# keyBoard_B_-.net
KiCad netlist of a schematic drawn in EAGLE
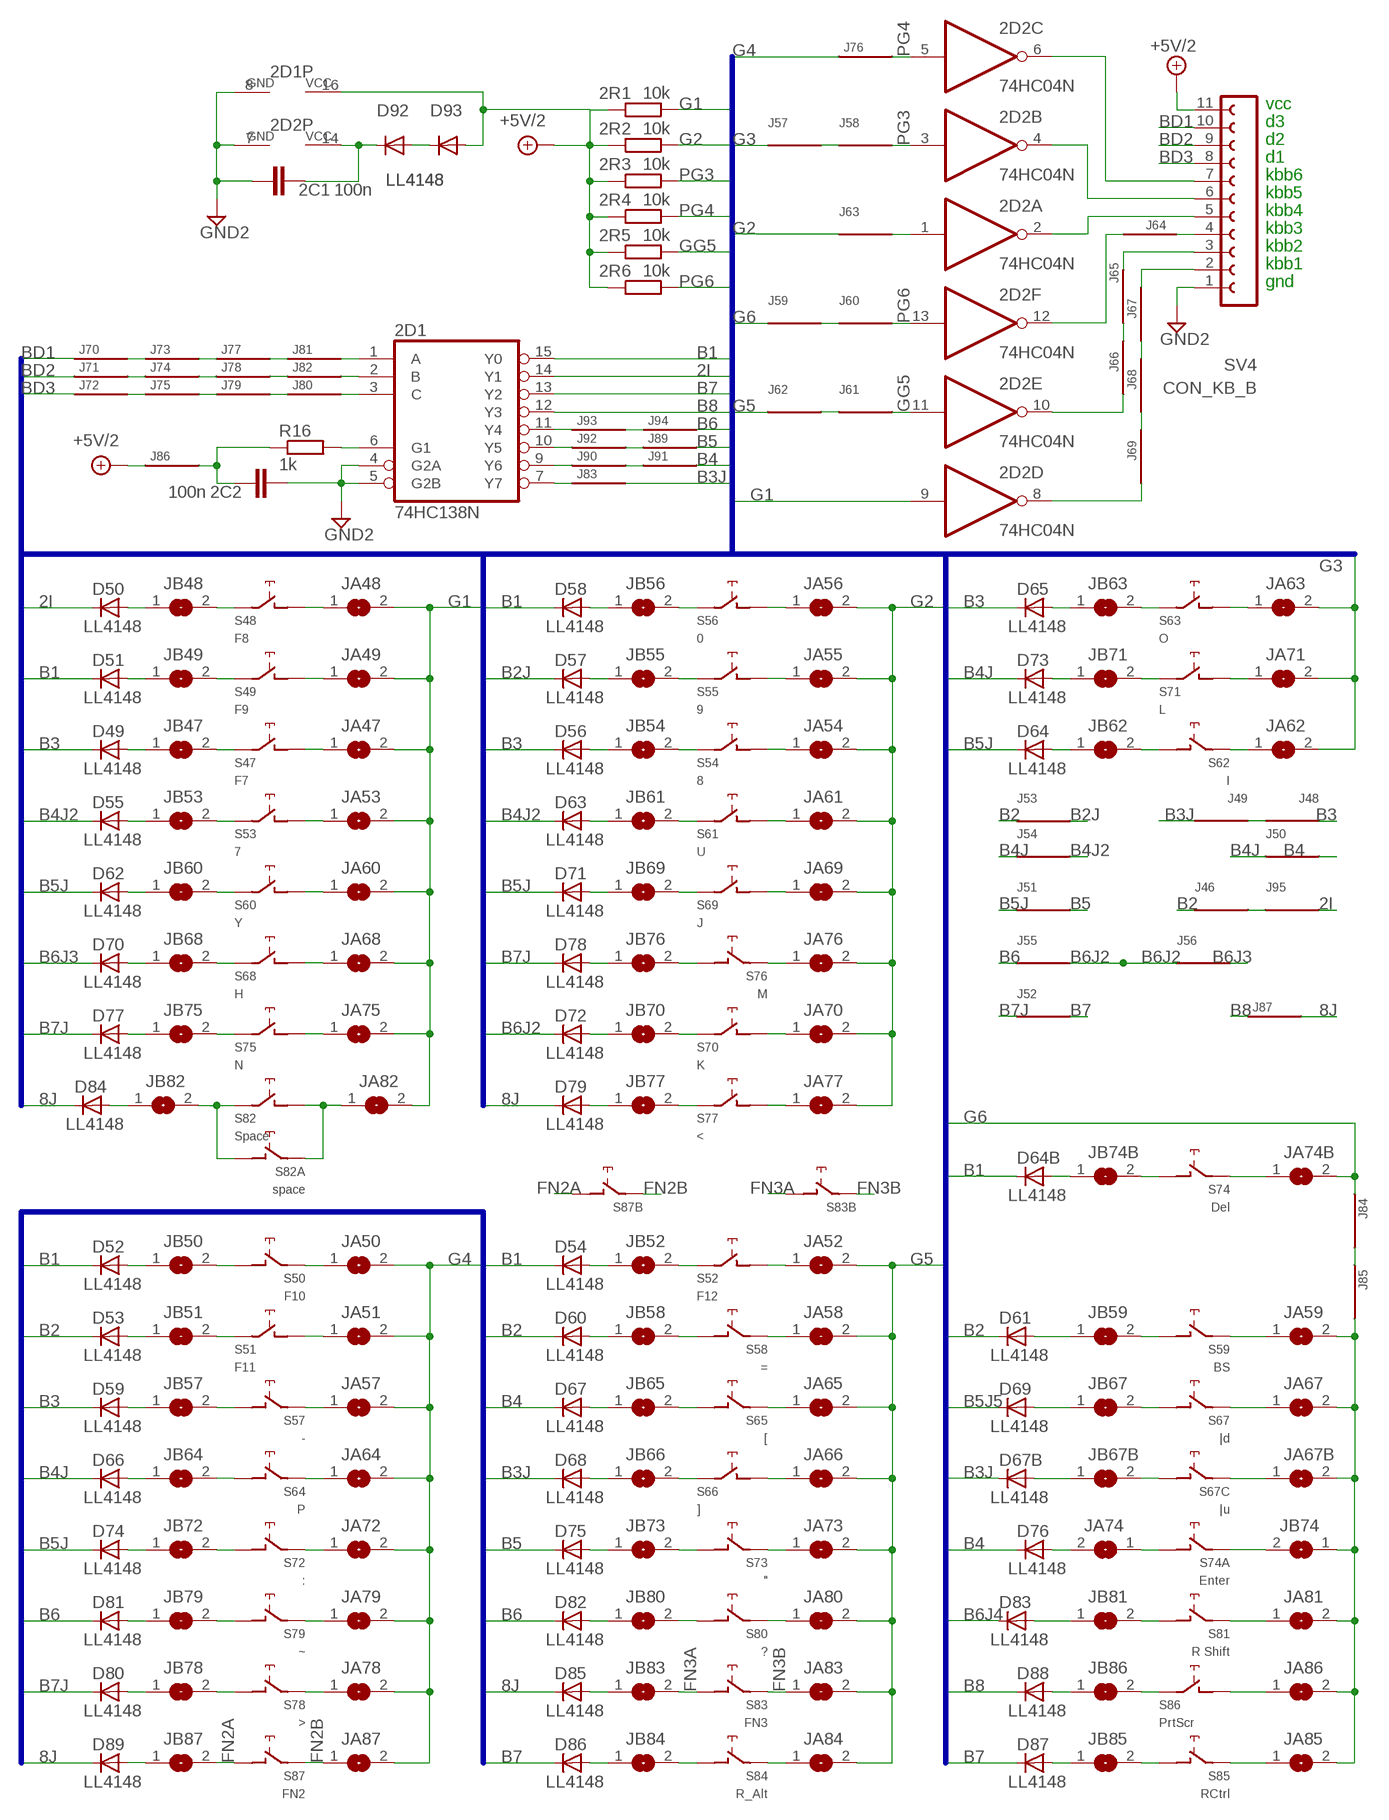
[diagram p0: schematic, sheet 1]

(export (version "E")
  (design (tool "Eeschema 10.0.6"))
  (components
    (comp (ref "2C1")
      (value "100n")
      (footprint "eagle-import:C1206")
      (libsource (lib "eagle-import") (part "C-EUC1206"))
    )
    (comp (ref "2C2")
      (value "100n")
      (footprint "eagle-import:C1206K")
      (libsource (lib "eagle-import") (part "C-EUC1206K"))
    )
    (comp (ref "2D1")
      (value "74HC138N")
      (footprint "eagle-import:DIL16")
      (libsource (lib "eagle-import") (part "74138NAC"))
    )
    (comp (ref "2D2")
      (value "74HC04N")
      (footprint "eagle-import:DIL14")
      (libsource (lib "eagle-import") (part "7404NALS"))
    )
    (comp (ref "2R1")
      (value "10k")
      (footprint "eagle-import:R0805")
      (libsource (lib "eagle-import") (part "R-EU_R0805"))
    )
    (comp (ref "2R2")
      (value "10k")
      (footprint "eagle-import:R0805")
      (libsource (lib "eagle-import") (part "R-EU_R0805"))
    )
    (comp (ref "2R3")
      (value "10k")
      (footprint "eagle-import:R0805")
      (libsource (lib "eagle-import") (part "R-EU_R0805"))
    )
    (comp (ref "2R4")
      (value "10k")
      (footprint "eagle-import:R1206W")
      (libsource (lib "eagle-import") (part "R-EU_R1206W"))
    )
    (comp (ref "2R5")
      (value "10k")
      (footprint "eagle-import:R0805")
      (libsource (lib "eagle-import") (part "R-EU_R0805"))
    )
    (comp (ref "2R6")
      (value "10k")
      (footprint "eagle-import:R0805")
      (libsource (lib "eagle-import") (part "R-EU_R0805"))
    )
    (comp (ref "D49")
      (value "LL4148")
      (footprint "eagle-import:SOD80C")
      (libsource (lib "eagle-import") (part "LL4148"))
    )
    (comp (ref "D50")
      (value "LL4148")
      (footprint "eagle-import:SOD80C")
      (libsource (lib "eagle-import") (part "LL4148"))
    )
    (comp (ref "D51")
      (value "LL4148")
      (footprint "eagle-import:SOD80C")
      (libsource (lib "eagle-import") (part "LL4148"))
    )
    (comp (ref "D52")
      (value "LL4148")
      (footprint "eagle-import:SOD80C")
      (libsource (lib "eagle-import") (part "LL4148"))
    )
    (comp (ref "D53")
      (value "LL4148")
      (footprint "eagle-import:SOD80C")
      (libsource (lib "eagle-import") (part "LL4148"))
    )
    (comp (ref "D54")
      (value "LL4148")
      (footprint "eagle-import:SOD80C")
      (libsource (lib "eagle-import") (part "LL4148"))
    )
    (comp (ref "D55")
      (value "LL4148")
      (footprint "eagle-import:SOD80C")
      (libsource (lib "eagle-import") (part "LL4148"))
    )
    (comp (ref "D56")
      (value "LL4148")
      (footprint "eagle-import:SOD80C")
      (libsource (lib "eagle-import") (part "LL4148"))
    )
    (comp (ref "D57")
      (value "LL4148")
      (footprint "eagle-import:SOD80C")
      (libsource (lib "eagle-import") (part "LL4148"))
    )
    (comp (ref "D58")
      (value "LL4148")
      (footprint "eagle-import:SOD80C")
      (libsource (lib "eagle-import") (part "LL4148"))
    )
    (comp (ref "D59")
      (value "LL4148")
      (footprint "eagle-import:SOD80C")
      (libsource (lib "eagle-import") (part "LL4148"))
    )
    (comp (ref "D60")
      (value "LL4148")
      (footprint "eagle-import:SOD80C")
      (libsource (lib "eagle-import") (part "LL4148"))
    )
    (comp (ref "D61")
      (value "LL4148")
      (footprint "eagle-import:SOD80C")
      (libsource (lib "eagle-import") (part "LL4148"))
    )
    (comp (ref "D62")
      (value "LL4148")
      (footprint "eagle-import:SOD80C")
      (libsource (lib "eagle-import") (part "LL4148"))
    )
    (comp (ref "D63")
      (value "LL4148")
      (footprint "eagle-import:SOD80C")
      (libsource (lib "eagle-import") (part "LL4148"))
    )
    (comp (ref "D64")
      (value "LL4148")
      (footprint "eagle-import:SOD80C")
      (libsource (lib "eagle-import") (part "LL4148"))
    )
    (comp (ref "D64B")
      (value "LL4148")
      (footprint "eagle-import:SOD80C")
      (libsource (lib "eagle-import") (part "LL4148"))
    )
    (comp (ref "D65")
      (value "LL4148")
      (footprint "eagle-import:SOD80C")
      (libsource (lib "eagle-import") (part "LL4148"))
    )
    (comp (ref "D66")
      (value "LL4148")
      (footprint "eagle-import:SOD80C")
      (libsource (lib "eagle-import") (part "LL4148"))
    )
    (comp (ref "D67")
      (value "LL4148")
      (footprint "eagle-import:SOD80C")
      (libsource (lib "eagle-import") (part "LL4148"))
    )
    (comp (ref "D67B")
      (value "LL4148")
      (footprint "eagle-import:SOD80C")
      (libsource (lib "eagle-import") (part "LL4148"))
    )
    (comp (ref "D68")
      (value "LL4148")
      (footprint "eagle-import:SOD80C")
      (libsource (lib "eagle-import") (part "LL4148"))
    )
    (comp (ref "D69")
      (value "LL4148")
      (footprint "eagle-import:SOD80C")
      (libsource (lib "eagle-import") (part "LL4148"))
    )
    (comp (ref "D70")
      (value "LL4148")
      (footprint "eagle-import:SOD80C")
      (libsource (lib "eagle-import") (part "LL4148"))
    )
    (comp (ref "D71")
      (value "LL4148")
      (footprint "eagle-import:SOD80C")
      (libsource (lib "eagle-import") (part "LL4148"))
    )
    (comp (ref "D72")
      (value "LL4148")
      (footprint "eagle-import:SOD80C")
      (libsource (lib "eagle-import") (part "LL4148"))
    )
    (comp (ref "D73")
      (value "LL4148")
      (footprint "eagle-import:SOD80C")
      (libsource (lib "eagle-import") (part "LL4148"))
    )
    (comp (ref "D74")
      (value "LL4148")
      (footprint "eagle-import:SOD80C")
      (libsource (lib "eagle-import") (part "LL4148"))
    )
    (comp (ref "D75")
      (value "LL4148")
      (footprint "eagle-import:SOD80C")
      (libsource (lib "eagle-import") (part "LL4148"))
    )
    (comp (ref "D76")
      (value "LL4148")
      (footprint "eagle-import:SOD80C")
      (libsource (lib "eagle-import") (part "LL4148"))
    )
    (comp (ref "D77")
      (value "LL4148")
      (footprint "eagle-import:SOD80C")
      (libsource (lib "eagle-import") (part "LL4148"))
    )
    (comp (ref "D78")
      (value "LL4148")
      (footprint "eagle-import:SOD80C")
      (libsource (lib "eagle-import") (part "LL4148"))
    )
    (comp (ref "D79")
      (value "LL4148")
      (footprint "eagle-import:SOD80C")
      (libsource (lib "eagle-import") (part "LL4148"))
    )
    (comp (ref "D80")
      (value "LL4148")
      (footprint "eagle-import:SOD80C")
      (libsource (lib "eagle-import") (part "LL4148"))
    )
    (comp (ref "D81")
      (value "LL4148")
      (footprint "eagle-import:SOD80C")
      (libsource (lib "eagle-import") (part "LL4148"))
    )
    (comp (ref "D82")
      (value "LL4148")
      (footprint "eagle-import:SOD80C")
      (libsource (lib "eagle-import") (part "LL4148"))
    )
    (comp (ref "D83")
      (value "LL4148")
      (footprint "eagle-import:SOD80C")
      (libsource (lib "eagle-import") (part "LL4148"))
    )
    (comp (ref "D84")
      (value "LL4148")
      (footprint "eagle-import:SOD80C")
      (libsource (lib "eagle-import") (part "LL4148"))
    )
    (comp (ref "D85")
      (value "LL4148")
      (footprint "eagle-import:SOD80C")
      (libsource (lib "eagle-import") (part "LL4148"))
    )
    (comp (ref "D86")
      (value "LL4148")
      (footprint "eagle-import:SOD80C")
      (libsource (lib "eagle-import") (part "LL4148"))
    )
    (comp (ref "D87")
      (value "LL4148")
      (footprint "eagle-import:SOD80C")
      (libsource (lib "eagle-import") (part "LL4148"))
    )
    (comp (ref "D88")
      (value "LL4148")
      (footprint "eagle-import:SOD80C")
      (libsource (lib "eagle-import") (part "LL4148"))
    )
    (comp (ref "D89")
      (value "LL4148")
      (footprint "eagle-import:SOD80C")
      (libsource (lib "eagle-import") (part "LL4148"))
    )
    (comp (ref "D92")
      (value "LL4148")
      (footprint "eagle-import:SOD80C")
      (libsource (lib "eagle-import") (part "LL4148"))
    )
    (comp (ref "D93")
      (value "LL4148")
      (footprint "eagle-import:SOD80C")
      (libsource (lib "eagle-import") (part "LL4148"))
    )
    (comp (ref "J46")
      (value "J")
      (footprint "eagle-import:R1206W")
      (libsource (lib "eagle-import") (part "J"))
    )
    (comp (ref "J48")
      (value "J")
      (footprint "eagle-import:R1206W")
      (libsource (lib "eagle-import") (part "J"))
    )
    (comp (ref "J49")
      (value "J")
      (footprint "eagle-import:R1206W")
      (libsource (lib "eagle-import") (part "J"))
    )
    (comp (ref "J50")
      (value "J")
      (footprint "eagle-import:R1206W")
      (libsource (lib "eagle-import") (part "J"))
    )
    (comp (ref "J51")
      (value "J")
      (footprint "eagle-import:R1206W")
      (libsource (lib "eagle-import") (part "J"))
    )
    (comp (ref "J52")
      (value "J")
      (footprint "eagle-import:R1206W")
      (libsource (lib "eagle-import") (part "J"))
    )
    (comp (ref "J53")
      (value "J")
      (footprint "eagle-import:R1206W")
      (libsource (lib "eagle-import") (part "J"))
    )
    (comp (ref "J54")
      (value "J")
      (footprint "eagle-import:R1206W")
      (libsource (lib "eagle-import") (part "J"))
    )
    (comp (ref "J55")
      (value "J")
      (footprint "eagle-import:R1206W")
      (libsource (lib "eagle-import") (part "J"))
    )
    (comp (ref "J56")
      (value "J")
      (footprint "eagle-import:R1206W")
      (libsource (lib "eagle-import") (part "J"))
    )
    (comp (ref "J57")
      (value "J")
      (footprint "eagle-import:R1206W")
      (libsource (lib "eagle-import") (part "J"))
    )
    (comp (ref "J58")
      (value "J")
      (footprint "eagle-import:R1206W")
      (libsource (lib "eagle-import") (part "J"))
    )
    (comp (ref "J59")
      (value "J")
      (footprint "eagle-import:R1206W")
      (libsource (lib "eagle-import") (part "J"))
    )
    (comp (ref "J60")
      (value "J")
      (footprint "eagle-import:R1206W")
      (libsource (lib "eagle-import") (part "J"))
    )
    (comp (ref "J61")
      (value "J")
      (footprint "eagle-import:R1206W")
      (libsource (lib "eagle-import") (part "J"))
    )
    (comp (ref "J62")
      (value "J")
      (footprint "eagle-import:R1206W")
      (libsource (lib "eagle-import") (part "J"))
    )
    (comp (ref "J63")
      (value "J")
      (footprint "eagle-import:R1206W")
      (libsource (lib "eagle-import") (part "J"))
    )
    (comp (ref "J64")
      (value "J")
      (footprint "eagle-import:R1206W")
      (libsource (lib "eagle-import") (part "J"))
    )
    (comp (ref "J65")
      (value "J")
      (footprint "eagle-import:R1206W")
      (libsource (lib "eagle-import") (part "J"))
    )
    (comp (ref "J66")
      (value "J")
      (footprint "eagle-import:R1206W")
      (libsource (lib "eagle-import") (part "J"))
    )
    (comp (ref "J67")
      (value "J")
      (footprint "eagle-import:R1206W")
      (libsource (lib "eagle-import") (part "J"))
    )
    (comp (ref "J68")
      (value "J")
      (footprint "eagle-import:R1206W")
      (libsource (lib "eagle-import") (part "J"))
    )
    (comp (ref "J69")
      (value "J")
      (footprint "eagle-import:R1206W")
      (libsource (lib "eagle-import") (part "J"))
    )
    (comp (ref "J70")
      (value "J")
      (footprint "eagle-import:R1206W")
      (libsource (lib "eagle-import") (part "J"))
    )
    (comp (ref "J71")
      (value "J")
      (footprint "eagle-import:R1206W")
      (libsource (lib "eagle-import") (part "J"))
    )
    (comp (ref "J72")
      (value "J")
      (footprint "eagle-import:R1206W")
      (libsource (lib "eagle-import") (part "J"))
    )
    (comp (ref "J73")
      (value "J")
      (footprint "eagle-import:R1206W")
      (libsource (lib "eagle-import") (part "J"))
    )
    (comp (ref "J74")
      (value "J")
      (footprint "eagle-import:R1206W")
      (libsource (lib "eagle-import") (part "J"))
    )
    (comp (ref "J75")
      (value "J")
      (footprint "eagle-import:R1206W")
      (libsource (lib "eagle-import") (part "J"))
    )
    (comp (ref "J76")
      (value "J")
      (footprint "eagle-import:R1206W")
      (libsource (lib "eagle-import") (part "J"))
    )
    (comp (ref "J77")
      (value "J")
      (footprint "eagle-import:R1206W")
      (libsource (lib "eagle-import") (part "J"))
    )
    (comp (ref "J78")
      (value "J")
      (footprint "eagle-import:R1206W")
      (libsource (lib "eagle-import") (part "J"))
    )
    (comp (ref "J79")
      (value "J")
      (footprint "eagle-import:R1206W")
      (libsource (lib "eagle-import") (part "J"))
    )
    (comp (ref "J80")
      (value "J")
      (footprint "eagle-import:R1206W")
      (libsource (lib "eagle-import") (part "J"))
    )
    (comp (ref "J81")
      (value "J")
      (footprint "eagle-import:R1206W")
      (libsource (lib "eagle-import") (part "J"))
    )
    (comp (ref "J82")
      (value "J")
      (footprint "eagle-import:R1206W")
      (libsource (lib "eagle-import") (part "J"))
    )
    (comp (ref "J83")
      (value "J")
      (footprint "eagle-import:R1206W")
      (libsource (lib "eagle-import") (part "J"))
    )
    (comp (ref "J84")
      (value "J")
      (footprint "eagle-import:R1206W")
      (libsource (lib "eagle-import") (part "J"))
    )
    (comp (ref "J85")
      (value "J")
      (footprint "eagle-import:R1206W")
      (libsource (lib "eagle-import") (part "J"))
    )
    (comp (ref "J86")
      (value "J")
      (footprint "eagle-import:R1206W")
      (libsource (lib "eagle-import") (part "J"))
    )
    (comp (ref "J87")
      (value "J")
      (footprint "eagle-import:R1206W")
      (libsource (lib "eagle-import") (part "J"))
    )
    (comp (ref "J89")
      (value "J")
      (footprint "eagle-import:R1206W")
      (libsource (lib "eagle-import") (part "J"))
    )
    (comp (ref "J90")
      (value "J")
      (footprint "eagle-import:R1206W")
      (libsource (lib "eagle-import") (part "J"))
    )
    (comp (ref "J91")
      (value "J")
      (footprint "eagle-import:R1206W")
      (libsource (lib "eagle-import") (part "J"))
    )
    (comp (ref "J92")
      (value "J")
      (footprint "eagle-import:R1206W")
      (libsource (lib "eagle-import") (part "J"))
    )
    (comp (ref "J93")
      (value "J")
      (footprint "eagle-import:R1206W")
      (libsource (lib "eagle-import") (part "J"))
    )
    (comp (ref "J94")
      (value "J")
      (footprint "eagle-import:R1206W")
      (libsource (lib "eagle-import") (part "J"))
    )
    (comp (ref "J95")
      (value "J")
      (footprint "eagle-import:R1206W")
      (libsource (lib "eagle-import") (part "J"))
    )
    (comp (ref "JA47")
      (value "SJ")
      (footprint "eagle-import:SJ")
      (libsource (lib "eagle-import") (part "SJ"))
    )
    (comp (ref "JA48")
      (value "SJ")
      (footprint "eagle-import:SJ")
      (libsource (lib "eagle-import") (part "SJ"))
    )
    (comp (ref "JA49")
      (value "SJ")
      (footprint "eagle-import:SJ")
      (libsource (lib "eagle-import") (part "SJ"))
    )
    (comp (ref "JA50")
      (value "SJ")
      (footprint "eagle-import:SJ")
      (libsource (lib "eagle-import") (part "SJ"))
    )
    (comp (ref "JA51")
      (value "SJ")
      (footprint "eagle-import:SJ")
      (libsource (lib "eagle-import") (part "SJ"))
    )
    (comp (ref "JA52")
      (value "SJ")
      (footprint "eagle-import:SJ")
      (libsource (lib "eagle-import") (part "SJ"))
    )
    (comp (ref "JA53")
      (value "SJ")
      (footprint "eagle-import:SJ")
      (libsource (lib "eagle-import") (part "SJ"))
    )
    (comp (ref "JA54")
      (value "SJ")
      (footprint "eagle-import:SJ")
      (libsource (lib "eagle-import") (part "SJ"))
    )
    (comp (ref "JA55")
      (value "SJ")
      (footprint "eagle-import:SJ")
      (libsource (lib "eagle-import") (part "SJ"))
    )
    (comp (ref "JA56")
      (value "SJ")
      (footprint "eagle-import:SJ")
      (libsource (lib "eagle-import") (part "SJ"))
    )
    (comp (ref "JA57")
      (value "SJ")
      (footprint "eagle-import:SJ")
      (libsource (lib "eagle-import") (part "SJ"))
    )
    (comp (ref "JA58")
      (value "SJ")
      (footprint "eagle-import:SJ")
      (libsource (lib "eagle-import") (part "SJ"))
    )
    (comp (ref "JA59")
      (value "SJ")
      (footprint "eagle-import:SJ")
      (libsource (lib "eagle-import") (part "SJ"))
    )
    (comp (ref "JA60")
      (value "SJ")
      (footprint "eagle-import:SJ")
      (libsource (lib "eagle-import") (part "SJ"))
    )
    (comp (ref "JA61")
      (value "SJ")
      (footprint "eagle-import:SJ")
      (libsource (lib "eagle-import") (part "SJ"))
    )
    (comp (ref "JA62")
      (value "SJ")
      (footprint "eagle-import:SJ")
      (libsource (lib "eagle-import") (part "SJ"))
    )
    (comp (ref "JA63")
      (value "SJ")
      (footprint "eagle-import:SJ")
      (libsource (lib "eagle-import") (part "SJ"))
    )
    (comp (ref "JA64")
      (value "SJ")
      (footprint "eagle-import:SJ")
      (libsource (lib "eagle-import") (part "SJ"))
    )
    (comp (ref "JA65")
      (value "SJ")
      (footprint "eagle-import:SJ")
      (libsource (lib "eagle-import") (part "SJ"))
    )
    (comp (ref "JA66")
      (value "SJ")
      (footprint "eagle-import:SJ")
      (libsource (lib "eagle-import") (part "SJ"))
    )
    (comp (ref "JA67")
      (value "SJ")
      (footprint "eagle-import:SJ")
      (libsource (lib "eagle-import") (part "SJ"))
    )
    (comp (ref "JA67B")
      (value "SJ")
      (footprint "eagle-import:SJ")
      (libsource (lib "eagle-import") (part "SJ"))
    )
    (comp (ref "JA68")
      (value "SJ")
      (footprint "eagle-import:SJ")
      (libsource (lib "eagle-import") (part "SJ"))
    )
    (comp (ref "JA69")
      (value "SJ")
      (footprint "eagle-import:SJ")
      (libsource (lib "eagle-import") (part "SJ"))
    )
    (comp (ref "JA70")
      (value "SJ")
      (footprint "eagle-import:SJ")
      (libsource (lib "eagle-import") (part "SJ"))
    )
    (comp (ref "JA71")
      (value "SJ")
      (footprint "eagle-import:SJ")
      (libsource (lib "eagle-import") (part "SJ"))
    )
    (comp (ref "JA72")
      (value "SJ")
      (footprint "eagle-import:SJ")
      (libsource (lib "eagle-import") (part "SJ"))
    )
    (comp (ref "JA73")
      (value "SJ")
      (footprint "eagle-import:SJ")
      (libsource (lib "eagle-import") (part "SJ"))
    )
    (comp (ref "JA74")
      (value "SJ")
      (footprint "eagle-import:SJ")
      (libsource (lib "eagle-import") (part "SJ"))
    )
    (comp (ref "JA74B")
      (value "SJ")
      (footprint "eagle-import:SJ")
      (libsource (lib "eagle-import") (part "SJ"))
    )
    (comp (ref "JA75")
      (value "SJ")
      (footprint "eagle-import:SJ")
      (libsource (lib "eagle-import") (part "SJ"))
    )
    (comp (ref "JA76")
      (value "SJ")
      (footprint "eagle-import:SJ")
      (libsource (lib "eagle-import") (part "SJ"))
    )
    (comp (ref "JA77")
      (value "SJ")
      (footprint "eagle-import:SJ")
      (libsource (lib "eagle-import") (part "SJ"))
    )
    (comp (ref "JA78")
      (value "SJ")
      (footprint "eagle-import:SJ")
      (libsource (lib "eagle-import") (part "SJ"))
    )
    (comp (ref "JA79")
      (value "SJ")
      (footprint "eagle-import:SJ")
      (libsource (lib "eagle-import") (part "SJ"))
    )
    (comp (ref "JA80")
      (value "SJ")
      (footprint "eagle-import:SJ")
      (libsource (lib "eagle-import") (part "SJ"))
    )
    (comp (ref "JA81")
      (value "SJ")
      (footprint "eagle-import:SJ")
      (libsource (lib "eagle-import") (part "SJ"))
    )
    (comp (ref "JA82")
      (value "SJ")
      (footprint "eagle-import:SJ")
      (libsource (lib "eagle-import") (part "SJ"))
    )
    (comp (ref "JA83")
      (value "SJ")
      (footprint "eagle-import:SJ")
      (libsource (lib "eagle-import") (part "SJ"))
    )
    (comp (ref "JA84")
      (value "SJ")
      (footprint "eagle-import:SJ")
      (libsource (lib "eagle-import") (part "SJ"))
    )
    (comp (ref "JA85")
      (value "SJ")
      (footprint "eagle-import:SJ")
      (libsource (lib "eagle-import") (part "SJ"))
    )
    (comp (ref "JA86")
      (value "SJ")
      (footprint "eagle-import:SJ")
      (libsource (lib "eagle-import") (part "SJ"))
    )
    (comp (ref "JA87")
      (value "SJ")
      (footprint "eagle-import:SJ")
      (libsource (lib "eagle-import") (part "SJ"))
    )
    (comp (ref "JB47")
      (value "SJ")
      (footprint "eagle-import:SJ")
      (libsource (lib "eagle-import") (part "SJ"))
    )
    (comp (ref "JB48")
      (value "SJ")
      (footprint "eagle-import:SJ")
      (libsource (lib "eagle-import") (part "SJ"))
    )
    (comp (ref "JB49")
      (value "SJ")
      (footprint "eagle-import:SJ")
      (libsource (lib "eagle-import") (part "SJ"))
    )
    (comp (ref "JB50")
      (value "SJ")
      (footprint "eagle-import:SJ")
      (libsource (lib "eagle-import") (part "SJ"))
    )
    (comp (ref "JB51")
      (value "SJ")
      (footprint "eagle-import:SJ")
      (libsource (lib "eagle-import") (part "SJ"))
    )
    (comp (ref "JB52")
      (value "SJ")
      (footprint "eagle-import:SJ")
      (libsource (lib "eagle-import") (part "SJ"))
    )
    (comp (ref "JB53")
      (value "SJ")
      (footprint "eagle-import:SJ")
      (libsource (lib "eagle-import") (part "SJ"))
    )
    (comp (ref "JB54")
      (value "SJ")
      (footprint "eagle-import:SJ")
      (libsource (lib "eagle-import") (part "SJ"))
    )
    (comp (ref "JB55")
      (value "SJ")
      (footprint "eagle-import:SJ")
      (libsource (lib "eagle-import") (part "SJ"))
    )
    (comp (ref "JB56")
      (value "SJ")
      (footprint "eagle-import:SJ")
      (libsource (lib "eagle-import") (part "SJ"))
    )
    (comp (ref "JB57")
      (value "SJ")
      (footprint "eagle-import:SJ")
      (libsource (lib "eagle-import") (part "SJ"))
    )
    (comp (ref "JB58")
      (value "SJ")
      (footprint "eagle-import:SJ")
      (libsource (lib "eagle-import") (part "SJ"))
    )
    (comp (ref "JB59")
      (value "SJ")
      (footprint "eagle-import:SJ")
      (libsource (lib "eagle-import") (part "SJ"))
    )
    (comp (ref "JB60")
      (value "SJ")
      (footprint "eagle-import:SJ")
      (libsource (lib "eagle-import") (part "SJ"))
    )
    (comp (ref "JB61")
      (value "SJ")
      (footprint "eagle-import:SJ")
      (libsource (lib "eagle-import") (part "SJ"))
    )
    (comp (ref "JB62")
      (value "SJ")
      (footprint "eagle-import:SJ")
      (libsource (lib "eagle-import") (part "SJ"))
    )
    (comp (ref "JB63")
      (value "SJ")
      (footprint "eagle-import:SJ")
      (libsource (lib "eagle-import") (part "SJ"))
    )
    (comp (ref "JB64")
      (value "SJ")
      (footprint "eagle-import:SJ")
      (libsource (lib "eagle-import") (part "SJ"))
    )
    (comp (ref "JB65")
      (value "SJ")
      (footprint "eagle-import:SJ")
      (libsource (lib "eagle-import") (part "SJ"))
    )
    (comp (ref "JB66")
      (value "SJ")
      (footprint "eagle-import:SJ")
      (libsource (lib "eagle-import") (part "SJ"))
    )
    (comp (ref "JB67")
      (value "SJ")
      (footprint "eagle-import:SJ")
      (libsource (lib "eagle-import") (part "SJ"))
    )
    (comp (ref "JB67B")
      (value "SJ")
      (footprint "eagle-import:SJ")
      (libsource (lib "eagle-import") (part "SJ"))
    )
    (comp (ref "JB68")
      (value "SJ")
      (footprint "eagle-import:SJ")
      (libsource (lib "eagle-import") (part "SJ"))
    )
    (comp (ref "JB69")
      (value "SJ")
      (footprint "eagle-import:SJ")
      (libsource (lib "eagle-import") (part "SJ"))
    )
    (comp (ref "JB70")
      (value "SJ")
      (footprint "eagle-import:SJ")
      (libsource (lib "eagle-import") (part "SJ"))
    )
    (comp (ref "JB71")
      (value "SJ")
      (footprint "eagle-import:SJ")
      (libsource (lib "eagle-import") (part "SJ"))
    )
    (comp (ref "JB72")
      (value "SJ")
      (footprint "eagle-import:SJ")
      (libsource (lib "eagle-import") (part "SJ"))
    )
    (comp (ref "JB73")
      (value "SJ")
      (footprint "eagle-import:SJ")
      (libsource (lib "eagle-import") (part "SJ"))
    )
    (comp (ref "JB74")
      (value "SJ")
      (footprint "eagle-import:SJ")
      (libsource (lib "eagle-import") (part "SJ"))
    )
    (comp (ref "JB74B")
      (value "SJ")
      (footprint "eagle-import:SJ")
      (libsource (lib "eagle-import") (part "SJ"))
    )
    (comp (ref "JB75")
      (value "SJ")
      (footprint "eagle-import:SJ")
      (libsource (lib "eagle-import") (part "SJ"))
    )
    (comp (ref "JB76")
      (value "SJ")
      (footprint "eagle-import:SJ")
      (libsource (lib "eagle-import") (part "SJ"))
    )
    (comp (ref "JB77")
      (value "SJ")
      (footprint "eagle-import:SJ")
      (libsource (lib "eagle-import") (part "SJ"))
    )
    (comp (ref "JB78")
      (value "SJ")
      (footprint "eagle-import:SJ")
      (libsource (lib "eagle-import") (part "SJ"))
    )
    (comp (ref "JB79")
      (value "SJ")
      (footprint "eagle-import:SJ")
      (libsource (lib "eagle-import") (part "SJ"))
    )
    (comp (ref "JB80")
      (value "SJ")
      (footprint "eagle-import:SJ")
      (libsource (lib "eagle-import") (part "SJ"))
    )
    (comp (ref "JB81")
      (value "SJ")
      (footprint "eagle-import:SJ")
      (libsource (lib "eagle-import") (part "SJ"))
    )
    (comp (ref "JB82")
      (value "SJ")
      (footprint "eagle-import:SJ")
      (libsource (lib "eagle-import") (part "SJ"))
    )
    (comp (ref "JB83")
      (value "SJ")
      (footprint "eagle-import:SJ")
      (libsource (lib "eagle-import") (part "SJ"))
    )
    (comp (ref "JB84")
      (value "SJ")
      (footprint "eagle-import:SJ")
      (libsource (lib "eagle-import") (part "SJ"))
    )
    (comp (ref "JB85")
      (value "SJ")
      (footprint "eagle-import:SJ")
      (libsource (lib "eagle-import") (part "SJ"))
    )
    (comp (ref "JB86")
      (value "SJ")
      (footprint "eagle-import:SJ")
      (libsource (lib "eagle-import") (part "SJ"))
    )
    (comp (ref "JB87")
      (value "SJ")
      (footprint "eagle-import:SJ")
      (libsource (lib "eagle-import") (part "SJ"))
    )
    (comp (ref "R16")
      (value "1k")
      (footprint "eagle-import:R1206W")
      (libsource (lib "eagle-import") (part "R-EU_R1206W"))
    )
    (comp (ref "S47")
      (value "F7")
      (footprint "eagle-import:CHERRY-MX-4P")
      (libsource (lib "eagle-import") (part "CHERRY-MX-4P"))
    )
    (comp (ref "S48")
      (value "F8")
      (footprint "eagle-import:CHERRY-MX-4P")
      (libsource (lib "eagle-import") (part "CHERRY-MX-4P"))
    )
    (comp (ref "S49")
      (value "F9")
      (footprint "eagle-import:CHERRY-MX-4P")
      (libsource (lib "eagle-import") (part "CHERRY-MX-4P"))
    )
    (comp (ref "S50")
      (value "F10")
      (footprint "eagle-import:CHERRY-MX-4P")
      (libsource (lib "eagle-import") (part "CHERRY-MX-4P"))
    )
    (comp (ref "S51")
      (value "F11")
      (footprint "eagle-import:CHERRY-MX-4P")
      (libsource (lib "eagle-import") (part "CHERRY-MX-4P"))
    )
    (comp (ref "S52")
      (value "F12")
      (footprint "eagle-import:CHERRY-MX-4P")
      (libsource (lib "eagle-import") (part "CHERRY-MX-4P"))
    )
    (comp (ref "S53")
      (value "7")
      (footprint "eagle-import:CHERRY-MX-4P")
      (libsource (lib "eagle-import") (part "CHERRY-MX-4P"))
    )
    (comp (ref "S54")
      (value "8")
      (footprint "eagle-import:CHERRY-MX-4P")
      (libsource (lib "eagle-import") (part "CHERRY-MX-4P"))
    )
    (comp (ref "S55")
      (value "9")
      (footprint "eagle-import:CHERRY-MX-4P")
      (libsource (lib "eagle-import") (part "CHERRY-MX-4P"))
    )
    (comp (ref "S56")
      (value "0")
      (footprint "eagle-import:CHERRY-MX-4P")
      (libsource (lib "eagle-import") (part "CHERRY-MX-4P"))
    )
    (comp (ref "S57")
      (value "-")
      (footprint "eagle-import:CHERRY-MX-4P")
      (libsource (lib "eagle-import") (part "CHERRY-MX-4P"))
    )
    (comp (ref "S58")
      (value "=")
      (footprint "eagle-import:CHERRY-MX-4P")
      (libsource (lib "eagle-import") (part "CHERRY-MX-4P"))
    )
    (comp (ref "S59")
      (value "BS")
      (footprint "eagle-import:CHERRY-MX-4P")
      (libsource (lib "eagle-import") (part "CHERRY-MX-4P"))
    )
    (comp (ref "S60")
      (value "Y")
      (footprint "eagle-import:CHERRY-MX-4P")
      (libsource (lib "eagle-import") (part "CHERRY-MX-4P"))
    )
    (comp (ref "S61")
      (value "U")
      (footprint "eagle-import:CHERRY-MX-4P")
      (libsource (lib "eagle-import") (part "CHERRY-MX-4P"))
    )
    (comp (ref "S62")
      (value "I")
      (footprint "eagle-import:CHERRY-MX-4P")
      (libsource (lib "eagle-import") (part "CHERRY-MX-4P"))
    )
    (comp (ref "S63")
      (value "O")
      (footprint "eagle-import:CHERRY-MX-4P")
      (libsource (lib "eagle-import") (part "CHERRY-MX-4P"))
    )
    (comp (ref "S64")
      (value "P")
      (footprint "eagle-import:CHERRY-MX-4P")
      (libsource (lib "eagle-import") (part "CHERRY-MX-4P"))
    )
    (comp (ref "S65")
      (value "[")
      (footprint "eagle-import:CHERRY-MX-4P")
      (libsource (lib "eagle-import") (part "CHERRY-MX-4P"))
    )
    (comp (ref "S66")
      (value "]")
      (footprint "eagle-import:CHERRY-MX-4P")
      (libsource (lib "eagle-import") (part "CHERRY-MX-4P"))
    )
    (comp (ref "S67")
      (value "|d")
      (footprint "eagle-import:CHERRY-MX-4P")
      (libsource (lib "eagle-import") (part "CHERRY-MX-4P"))
    )
    (comp (ref "S67C")
      (value "|u")
      (footprint "eagle-import:CHERRY-MX-4P")
      (libsource (lib "eagle-import") (part "CHERRY-MX-4P"))
    )
    (comp (ref "S68")
      (value "H")
      (footprint "eagle-import:CHERRY-MX-4P")
      (libsource (lib "eagle-import") (part "CHERRY-MX-4P"))
    )
    (comp (ref "S69")
      (value "J")
      (footprint "eagle-import:CHERRY-MX-4P")
      (libsource (lib "eagle-import") (part "CHERRY-MX-4P"))
    )
    (comp (ref "S70")
      (value "K")
      (footprint "eagle-import:CHERRY-MX-4P")
      (libsource (lib "eagle-import") (part "CHERRY-MX-4P"))
    )
    (comp (ref "S71")
      (value "L")
      (footprint "eagle-import:CHERRY-MX-4P")
      (libsource (lib "eagle-import") (part "CHERRY-MX-4P"))
    )
    (comp (ref "S72")
      (value ":")
      (footprint "eagle-import:CHERRY-MX-4P")
      (libsource (lib "eagle-import") (part "CHERRY-MX-4P"))
    )
    (comp (ref "S73")
      (value "\"")
      (footprint "eagle-import:CHERRY-MX-4P")
      (libsource (lib "eagle-import") (part "CHERRY-MX-4P"))
    )
    (comp (ref "S74")
      (value "Del")
      (footprint "eagle-import:CHERRY-MX-4P")
      (libsource (lib "eagle-import") (part "CHERRY-MX-4P"))
    )
    (comp (ref "S74A")
      (value "Enter")
      (footprint "eagle-import:CHERRY-MX-4P")
      (libsource (lib "eagle-import") (part "CHERRY-MX-4P"))
    )
    (comp (ref "S75")
      (value "N")
      (footprint "eagle-import:CHERRY-MX-4P")
      (libsource (lib "eagle-import") (part "CHERRY-MX-4P"))
    )
    (comp (ref "S76")
      (value "M")
      (footprint "eagle-import:CHERRY-MX-4P")
      (libsource (lib "eagle-import") (part "CHERRY-MX-4P"))
    )
    (comp (ref "S77")
      (value "<")
      (footprint "eagle-import:CHERRY-MX-4P")
      (libsource (lib "eagle-import") (part "CHERRY-MX-4P"))
    )
    (comp (ref "S78")
      (value ">")
      (footprint "eagle-import:CHERRY-MX-4P")
      (libsource (lib "eagle-import") (part "CHERRY-MX-4P"))
    )
    (comp (ref "S79")
      (value "~")
      (footprint "eagle-import:CHERRY-MX-4P")
      (libsource (lib "eagle-import") (part "CHERRY-MX-4P"))
    )
    (comp (ref "S80")
      (value "?")
      (footprint "eagle-import:CHERRY-MX-4P")
      (libsource (lib "eagle-import") (part "CHERRY-MX-4P"))
    )
    (comp (ref "S81")
      (value "R Shift")
      (footprint "eagle-import:CHERRY-MX-4P")
      (libsource (lib "eagle-import") (part "CHERRY-MX-4P"))
    )
    (comp (ref "S82")
      (value "Space")
      (footprint "eagle-import:CHERRY-MX-4P")
      (libsource (lib "eagle-import") (part "CHERRY-MX-4P"))
    )
    (comp (ref "S82A")
      (value "space")
      (footprint "eagle-import:CHERRY-MX")
      (libsource (lib "eagle-import") (part "CHERRY-MX"))
    )
    (comp (ref "S83")
      (value "FN3")
      (footprint "eagle-import:CHERRY-MX-4P")
      (libsource (lib "eagle-import") (part "CHERRY-MX-4P"))
    )
    (comp (ref "S83B")
      (value "CHERRY-MX")
      (footprint "eagle-import:CHERRY-MX")
      (libsource (lib "eagle-import") (part "CHERRY-MX"))
    )
    (comp (ref "S84")
      (value "R_Alt")
      (footprint "eagle-import:CHERRY-MX-4P")
      (libsource (lib "eagle-import") (part "CHERRY-MX-4P"))
    )
    (comp (ref "S85")
      (value "RCtrl")
      (footprint "eagle-import:CHERRY-MX-4P")
      (libsource (lib "eagle-import") (part "CHERRY-MX-4P"))
    )
    (comp (ref "S86")
      (value "PrtScr")
      (footprint "eagle-import:CHERRY-MX-4P")
      (libsource (lib "eagle-import") (part "CHERRY-MX-4P"))
    )
    (comp (ref "S87")
      (value "FN2")
      (footprint "eagle-import:CHERRY-MX-4P")
      (libsource (lib "eagle-import") (part "CHERRY-MX-4P"))
    )
    (comp (ref "S87B")
      (value "CHERRY-MX")
      (footprint "eagle-import:CHERRY-MX")
      (libsource (lib "eagle-import") (part "CHERRY-MX"))
    )
    (comp (ref "SV4")
      (value "CON_KB_B")
      (footprint "eagle-import:FE12")
      (libsource (lib "eagle-import") (part "FE12-1"))
    )
  )
  (nets
    (net (code "4") (name "+5V{slash}2") (class "Default")
      (node (ref "2D1") (pin "16") (pinfunction "VCC_16") (pintype "power_in"))
      (node (ref "2R1") (pin "1") (pinfunction "1_1") (pintype "passive"))
      (node (ref "2R2") (pin "1") (pinfunction "1_1") (pintype "passive"))
      (node (ref "2R3") (pin "1") (pinfunction "1_1") (pintype "passive"))
      (node (ref "2R4") (pin "1") (pinfunction "1_1") (pintype "passive"))
      (node (ref "2R5") (pin "1") (pinfunction "1_1") (pintype "passive"))
      (node (ref "2R6") (pin "1") (pinfunction "1_1") (pintype "passive"))
      (node (ref "D93") (pin "A") (pinfunction "A_A") (pintype "passive"))
      (node (ref "J86") (pin "2") (pinfunction "P$2_2") (pintype "bidirectional"))
      (node (ref "SV4") (pin "11") (pinfunction "11_11") (pintype "passive"))
    )
    (net (code "5") (name "/2I") (class "Default")
      (node (ref "2D1") (pin "14") (pinfunction "Y1_14") (pintype "output"))
      (node (ref "D50") (pin "C") (pinfunction "C_C") (pintype "passive"))
      (node (ref "J95") (pin "1") (pinfunction "P$1_1") (pintype "bidirectional"))
    )
    (net (code "6") (name "/8J") (class "Default")
      (node (ref "D79") (pin "C") (pinfunction "C_C") (pintype "passive"))
      (node (ref "D84") (pin "C") (pinfunction "C_C") (pintype "passive"))
      (node (ref "D85") (pin "C") (pinfunction "C_C") (pintype "passive"))
      (node (ref "D89") (pin "C") (pinfunction "C_C") (pintype "passive"))
      (node (ref "J87") (pin "1") (pinfunction "P$1_1") (pintype "bidirectional"))
    )
    (net (code "7") (name "/B1") (class "Default")
      (node (ref "2D1") (pin "15") (pinfunction "Y0_15") (pintype "output"))
      (node (ref "D51") (pin "C") (pinfunction "C_C") (pintype "passive"))
      (node (ref "D52") (pin "C") (pinfunction "C_C") (pintype "passive"))
      (node (ref "D54") (pin "C") (pinfunction "C_C") (pintype "passive"))
      (node (ref "D58") (pin "C") (pinfunction "C_C") (pintype "passive"))
      (node (ref "D64B") (pin "C") (pinfunction "C_C") (pintype "passive"))
    )
    (net (code "8") (name "/B2") (class "Default")
      (node (ref "D53") (pin "C") (pinfunction "C_C") (pintype "passive"))
      (node (ref "D60") (pin "C") (pinfunction "C_C") (pintype "passive"))
      (node (ref "D61") (pin "C") (pinfunction "C_C") (pintype "passive"))
      (node (ref "J46") (pin "2") (pinfunction "P$2_2") (pintype "bidirectional"))
      (node (ref "J53") (pin "2") (pinfunction "P$2_2") (pintype "bidirectional"))
    )
    (net (code "9") (name "/B2J") (class "Default")
      (node (ref "D57") (pin "C") (pinfunction "C_C") (pintype "passive"))
      (node (ref "J53") (pin "1") (pinfunction "P$1_1") (pintype "bidirectional"))
    )
    (net (code "10") (name "/B3") (class "Default")
      (node (ref "D49") (pin "C") (pinfunction "C_C") (pintype "passive"))
      (node (ref "D56") (pin "C") (pinfunction "C_C") (pintype "passive"))
      (node (ref "D59") (pin "C") (pinfunction "C_C") (pintype "passive"))
      (node (ref "D65") (pin "C") (pinfunction "C_C") (pintype "passive"))
      (node (ref "J48") (pin "2") (pinfunction "P$2_2") (pintype "bidirectional"))
    )
    (net (code "11") (name "/B3J") (class "Default")
      (node (ref "D67B") (pin "C") (pinfunction "C_C") (pintype "passive"))
      (node (ref "D68") (pin "C") (pinfunction "C_C") (pintype "passive"))
      (node (ref "J49") (pin "1") (pinfunction "P$1_1") (pintype "bidirectional"))
      (node (ref "J83") (pin "1") (pinfunction "P$1_1") (pintype "bidirectional"))
    )
    (net (code "12") (name "/B4") (class "Default")
      (node (ref "D67") (pin "C") (pinfunction "C_C") (pintype "passive"))
      (node (ref "D76") (pin "C") (pinfunction "C_C") (pintype "passive"))
      (node (ref "J50") (pin "1") (pinfunction "P$1_1") (pintype "bidirectional"))
      (node (ref "J91") (pin "1") (pinfunction "P$1_1") (pintype "bidirectional"))
    )
    (net (code "13") (name "/B4J") (class "Default")
      (node (ref "D66") (pin "C") (pinfunction "C_C") (pintype "passive"))
      (node (ref "D73") (pin "C") (pinfunction "C_C") (pintype "passive"))
      (node (ref "J50") (pin "2") (pinfunction "P$2_2") (pintype "bidirectional"))
      (node (ref "J54") (pin "2") (pinfunction "P$2_2") (pintype "bidirectional"))
    )
    (net (code "14") (name "/B4J2") (class "Default")
      (node (ref "D55") (pin "C") (pinfunction "C_C") (pintype "passive"))
      (node (ref "D63") (pin "C") (pinfunction "C_C") (pintype "passive"))
      (node (ref "J54") (pin "1") (pinfunction "P$1_1") (pintype "bidirectional"))
    )
    (net (code "15") (name "/B5") (class "Default")
      (node (ref "D75") (pin "C") (pinfunction "C_C") (pintype "passive"))
      (node (ref "J51") (pin "1") (pinfunction "P$1_1") (pintype "bidirectional"))
      (node (ref "J89") (pin "1") (pinfunction "P$1_1") (pintype "bidirectional"))
    )
    (net (code "16") (name "/B5J") (class "Default")
      (node (ref "D62") (pin "C") (pinfunction "C_C") (pintype "passive"))
      (node (ref "D64") (pin "C") (pinfunction "C_C") (pintype "passive"))
      (node (ref "D71") (pin "C") (pinfunction "C_C") (pintype "passive"))
      (node (ref "D74") (pin "C") (pinfunction "C_C") (pintype "passive"))
      (node (ref "J51") (pin "2") (pinfunction "P$2_2") (pintype "bidirectional"))
    )
    (net (code "17") (name "/B5J5") (class "Default")
      (node (ref "2D1") (pin "10") (pinfunction "Y5_10") (pintype "output"))
      (node (ref "D69") (pin "C") (pinfunction "C_C") (pintype "passive"))
      (node (ref "J92") (pin "2") (pinfunction "P$2_2") (pintype "bidirectional"))
    )
    (net (code "18") (name "/B6") (class "Default")
      (node (ref "D81") (pin "C") (pinfunction "C_C") (pintype "passive"))
      (node (ref "D82") (pin "C") (pinfunction "C_C") (pintype "passive"))
      (node (ref "J55") (pin "2") (pinfunction "P$2_2") (pintype "bidirectional"))
      (node (ref "J94") (pin "1") (pinfunction "P$1_1") (pintype "bidirectional"))
    )
    (net (code "19") (name "/B6J2") (class "Default")
      (node (ref "D72") (pin "C") (pinfunction "C_C") (pintype "passive"))
      (node (ref "J55") (pin "1") (pinfunction "P$1_1") (pintype "bidirectional"))
      (node (ref "J56") (pin "2") (pinfunction "P$2_2") (pintype "bidirectional"))
    )
    (net (code "20") (name "/B6J3") (class "Default")
      (node (ref "D70") (pin "C") (pinfunction "C_C") (pintype "passive"))
      (node (ref "J56") (pin "1") (pinfunction "P$1_1") (pintype "bidirectional"))
    )
    (net (code "21") (name "/B6J4") (class "Default")
      (node (ref "D83") (pin "C") (pinfunction "C_C") (pintype "passive"))
      (node (ref "J93") (pin "1") (pinfunction "P$1_1") (pintype "bidirectional"))
      (node (ref "J94") (pin "2") (pinfunction "P$2_2") (pintype "bidirectional"))
    )
    (net (code "22") (name "/B7") (class "Default")
      (node (ref "2D1") (pin "13") (pinfunction "Y2_13") (pintype "output"))
      (node (ref "D86") (pin "C") (pinfunction "C_C") (pintype "passive"))
      (node (ref "D87") (pin "C") (pinfunction "C_C") (pintype "passive"))
      (node (ref "J52") (pin "1") (pinfunction "P$1_1") (pintype "bidirectional"))
    )
    (net (code "23") (name "/B7J") (class "Default")
      (node (ref "D77") (pin "C") (pinfunction "C_C") (pintype "passive"))
      (node (ref "D78") (pin "C") (pinfunction "C_C") (pintype "passive"))
      (node (ref "D80") (pin "C") (pinfunction "C_C") (pintype "passive"))
      (node (ref "J52") (pin "2") (pinfunction "P$2_2") (pintype "bidirectional"))
    )
    (net (code "24") (name "/B8") (class "Default")
      (node (ref "2D1") (pin "12") (pinfunction "Y3_12") (pintype "output"))
      (node (ref "D88") (pin "C") (pinfunction "C_C") (pintype "passive"))
      (node (ref "J87") (pin "2") (pinfunction "P$2_2") (pintype "bidirectional"))
    )
    (net (code "25") (name "/BD1") (class "Default")
      (node (ref "J70") (pin "2") (pinfunction "P$2_2") (pintype "bidirectional"))
      (node (ref "SV4") (pin "10") (pinfunction "10_10") (pintype "passive"))
    )
    (net (code "26") (name "/BD2") (class "Default")
      (node (ref "J71") (pin "2") (pinfunction "P$2_2") (pintype "bidirectional"))
      (node (ref "SV4") (pin "9") (pinfunction "9_9") (pintype "passive"))
    )
    (net (code "27") (name "/BD3") (class "Default")
      (node (ref "J72") (pin "2") (pinfunction "P$2_2") (pintype "bidirectional"))
      (node (ref "SV4") (pin "8") (pinfunction "8_8") (pintype "passive"))
    )
    (net (code "28") (name "/FN2A") (class "Default")
      (node (ref "JB87") (pin "2") (pinfunction "2_2") (pintype "passive"))
      (node (ref "S87") (pin "SW2") (pinfunction "PIN-2_SW2") (pintype "passive"))
      (node (ref "S87B") (pin "SW2") (pinfunction "PIN-2_SW2") (pintype "passive"))
    )
    (net (code "29") (name "/FN2B") (class "Default")
      (node (ref "JA87") (pin "1") (pinfunction "1_1") (pintype "passive"))
      (node (ref "S87") (pin "SW1") (pinfunction "PIN-1_SW1") (pintype "passive"))
      (node (ref "S87B") (pin "SW1") (pinfunction "PIN-1_SW1") (pintype "passive"))
    )
    (net (code "30") (name "/FN3A") (class "Default")
      (node (ref "JB83") (pin "2") (pinfunction "2_2") (pintype "passive"))
      (node (ref "S83") (pin "SW2") (pinfunction "PIN-2_SW2") (pintype "passive"))
      (node (ref "S83B") (pin "SW2") (pinfunction "PIN-2_SW2") (pintype "passive"))
    )
    (net (code "31") (name "/FN3B") (class "Default")
      (node (ref "JA83") (pin "1") (pinfunction "1_1") (pintype "passive"))
      (node (ref "S83") (pin "SW1") (pinfunction "PIN-1_SW1") (pintype "passive"))
      (node (ref "S83B") (pin "SW1") (pinfunction "PIN-1_SW1") (pintype "passive"))
    )
    (net (code "32") (name "/G1") (class "Default")
      (node (ref "2D2") (pin "9") (pinfunction "I_9") (pintype "input"))
      (node (ref "2R1") (pin "2") (pinfunction "2_2") (pintype "passive"))
      (node (ref "JA47") (pin "2") (pinfunction "2_2") (pintype "passive"))
      (node (ref "JA48") (pin "2") (pinfunction "2_2") (pintype "passive"))
      (node (ref "JA49") (pin "2") (pinfunction "2_2") (pintype "passive"))
      (node (ref "JA53") (pin "2") (pinfunction "2_2") (pintype "passive"))
      (node (ref "JA60") (pin "2") (pinfunction "2_2") (pintype "passive"))
      (node (ref "JA68") (pin "2") (pinfunction "2_2") (pintype "passive"))
      (node (ref "JA75") (pin "2") (pinfunction "2_2") (pintype "passive"))
      (node (ref "JA82") (pin "2") (pinfunction "2_2") (pintype "passive"))
    )
    (net (code "33") (name "/G2") (class "Default")
      (node (ref "2R2") (pin "2") (pinfunction "2_2") (pintype "passive"))
      (node (ref "J63") (pin "2") (pinfunction "P$2_2") (pintype "bidirectional"))
      (node (ref "JA54") (pin "2") (pinfunction "2_2") (pintype "passive"))
      (node (ref "JA55") (pin "2") (pinfunction "2_2") (pintype "passive"))
      (node (ref "JA56") (pin "2") (pinfunction "2_2") (pintype "passive"))
      (node (ref "JA61") (pin "2") (pinfunction "2_2") (pintype "passive"))
      (node (ref "JA69") (pin "2") (pinfunction "2_2") (pintype "passive"))
      (node (ref "JA70") (pin "2") (pinfunction "2_2") (pintype "passive"))
      (node (ref "JA76") (pin "2") (pinfunction "2_2") (pintype "passive"))
      (node (ref "JA77") (pin "2") (pinfunction "2_2") (pintype "passive"))
    )
    (net (code "34") (name "/G3") (class "Default")
      (node (ref "J57") (pin "2") (pinfunction "P$2_2") (pintype "bidirectional"))
      (node (ref "JA62") (pin "2") (pinfunction "2_2") (pintype "passive"))
      (node (ref "JA63") (pin "2") (pinfunction "2_2") (pintype "passive"))
      (node (ref "JA71") (pin "2") (pinfunction "2_2") (pintype "passive"))
    )
    (net (code "35") (name "/G4") (class "Default")
      (node (ref "J76") (pin "2") (pinfunction "P$2_2") (pintype "bidirectional"))
      (node (ref "JA50") (pin "2") (pinfunction "2_2") (pintype "passive"))
      (node (ref "JA51") (pin "2") (pinfunction "2_2") (pintype "passive"))
      (node (ref "JA57") (pin "2") (pinfunction "2_2") (pintype "passive"))
      (node (ref "JA64") (pin "2") (pinfunction "2_2") (pintype "passive"))
      (node (ref "JA72") (pin "2") (pinfunction "2_2") (pintype "passive"))
      (node (ref "JA78") (pin "2") (pinfunction "2_2") (pintype "passive"))
      (node (ref "JA79") (pin "2") (pinfunction "2_2") (pintype "passive"))
      (node (ref "JA87") (pin "2") (pinfunction "2_2") (pintype "passive"))
    )
    (net (code "36") (name "/G5") (class "Default")
      (node (ref "J62") (pin "2") (pinfunction "P$2_2") (pintype "bidirectional"))
      (node (ref "JA52") (pin "2") (pinfunction "2_2") (pintype "passive"))
      (node (ref "JA58") (pin "2") (pinfunction "2_2") (pintype "passive"))
      (node (ref "JA65") (pin "2") (pinfunction "2_2") (pintype "passive"))
      (node (ref "JA66") (pin "2") (pinfunction "2_2") (pintype "passive"))
      (node (ref "JA73") (pin "2") (pinfunction "2_2") (pintype "passive"))
      (node (ref "JA80") (pin "2") (pinfunction "2_2") (pintype "passive"))
      (node (ref "JA83") (pin "2") (pinfunction "2_2") (pintype "passive"))
      (node (ref "JA84") (pin "2") (pinfunction "2_2") (pintype "passive"))
    )
    (net (code "37") (name "/G6") (class "Default")
      (node (ref "J59") (pin "2") (pinfunction "P$2_2") (pintype "bidirectional"))
      (node (ref "J84") (pin "2") (pinfunction "P$2_2") (pintype "bidirectional"))
      (node (ref "JA74B") (pin "2") (pinfunction "2_2") (pintype "passive"))
    )
    (net (code "38") (name "/GG5") (class "Default")
      (node (ref "2D2") (pin "11") (pinfunction "I_11") (pintype "input"))
      (node (ref "2R5") (pin "2") (pinfunction "2_2") (pintype "passive"))
      (node (ref "J61") (pin "1") (pinfunction "P$1_1") (pintype "bidirectional"))
    )
    (net (code "39") (name "/PG3") (class "Default")
      (node (ref "2D2") (pin "3") (pinfunction "I_3") (pintype "input"))
      (node (ref "2R3") (pin "2") (pinfunction "2_2") (pintype "passive"))
      (node (ref "J58") (pin "1") (pinfunction "P$1_1") (pintype "bidirectional"))
    )
    (net (code "40") (name "/PG4") (class "Default")
      (node (ref "2D2") (pin "5") (pinfunction "I_5") (pintype "input"))
      (node (ref "2R4") (pin "2") (pinfunction "2_2") (pintype "passive"))
      (node (ref "J76") (pin "1") (pinfunction "P$1_1") (pintype "bidirectional"))
    )
    (net (code "41") (name "/PG6") (class "Default")
      (node (ref "2D2") (pin "13") (pinfunction "I_13") (pintype "input"))
      (node (ref "2R6") (pin "2") (pinfunction "2_2") (pintype "passive"))
      (node (ref "J60") (pin "1") (pinfunction "P$1_1") (pintype "bidirectional"))
    )
    (net (code "43") (name "GND2") (class "Default")
      (node (ref "2C1") (pin "2") (pinfunction "2_2") (pintype "passive"))
      (node (ref "2C2") (pin "2") (pinfunction "2_2") (pintype "passive"))
      (node (ref "2D1") (pin "4") (pinfunction "G2A_4") (pintype "input"))
      (node (ref "2D1") (pin "5") (pinfunction "G2B_5") (pintype "input"))
      (node (ref "2D1") (pin "8") (pinfunction "GND_8") (pintype "power_in"))
      (node (ref "2D2") (pin "7") (pinfunction "GND_7") (pintype "power_in"))
      (node (ref "SV4") (pin "1") (pinfunction "1_1") (pintype "passive"))
    )
    (net (code "44") (name "Net-(2D1A-A)") (class "Default")
      (node (ref "2D1") (pin "1") (pinfunction "A_1") (pintype "input"))
      (node (ref "J81") (pin "1") (pinfunction "P$1_1") (pintype "bidirectional"))
    )
    (net (code "45") (name "Net-(2D1A-B)") (class "Default")
      (node (ref "2D1") (pin "2") (pinfunction "B_2") (pintype "input"))
      (node (ref "J82") (pin "1") (pinfunction "P$1_1") (pintype "bidirectional"))
    )
    (net (code "46") (name "Net-(2D1A-C)") (class "Default")
      (node (ref "2D1") (pin "3") (pinfunction "C_3") (pintype "input"))
      (node (ref "J80") (pin "1") (pinfunction "P$1_1") (pintype "bidirectional"))
    )
    (net (code "47") (name "Net-(2D1A-G1)") (class "Default")
      (node (ref "2D1") (pin "6") (pinfunction "G1_6") (pintype "input"))
      (node (ref "R16") (pin "2") (pinfunction "2_2") (pintype "passive"))
    )
    (net (code "48") (name "Net-(2D1A-Y4)") (class "Default")
      (node (ref "2D1") (pin "11") (pinfunction "Y4_11") (pintype "output"))
      (node (ref "J93") (pin "2") (pinfunction "P$2_2") (pintype "bidirectional"))
    )
    (net (code "49") (name "Net-(2D1A-Y6)") (class "Default")
      (node (ref "2D1") (pin "9") (pinfunction "Y6_9") (pintype "output"))
      (node (ref "J90") (pin "2") (pinfunction "P$2_2") (pintype "bidirectional"))
    )
    (net (code "50") (name "Net-(2D1A-Y7)") (class "Default")
      (node (ref "2D1") (pin "7") (pinfunction "Y7_7") (pintype "output"))
      (node (ref "J83") (pin "2") (pinfunction "P$2_2") (pintype "bidirectional"))
    )
    (net (code "51") (name "Net-(2D2A-I)") (class "Default")
      (node (ref "2D2") (pin "1") (pinfunction "I_1") (pintype "input"))
      (node (ref "J63") (pin "1") (pinfunction "P$1_1") (pintype "bidirectional"))
    )
    (net (code "52") (name "Net-(2D2A-O)") (class "Default")
      (node (ref "2D2") (pin "2") (pinfunction "O_2") (pintype "output"))
      (node (ref "SV4") (pin "5") (pinfunction "5_5") (pintype "passive"))
    )
    (net (code "53") (name "Net-(2D2B-O)") (class "Default")
      (node (ref "2D2") (pin "4") (pinfunction "O_4") (pintype "output"))
      (node (ref "SV4") (pin "6") (pinfunction "6_6") (pintype "passive"))
    )
    (net (code "54") (name "Net-(2D2C-O)") (class "Default")
      (node (ref "2D2") (pin "6") (pinfunction "O_6") (pintype "output"))
      (node (ref "SV4") (pin "7") (pinfunction "7_7") (pintype "passive"))
    )
    (net (code "55") (name "Net-(2D2D-O)") (class "Default")
      (node (ref "2D2") (pin "8") (pinfunction "O_8") (pintype "output"))
      (node (ref "J69") (pin "2") (pinfunction "P$2_2") (pintype "bidirectional"))
    )
    (net (code "56") (name "Net-(2D2E-O)") (class "Default")
      (node (ref "2D2") (pin "10") (pinfunction "O_10") (pintype "output"))
      (node (ref "J66") (pin "2") (pinfunction "P$2_2") (pintype "bidirectional"))
    )
    (net (code "57") (name "Net-(2D2F-O)") (class "Default")
      (node (ref "2D2") (pin "12") (pinfunction "O_12") (pintype "output"))
      (node (ref "J64") (pin "2") (pinfunction "P$2_2") (pintype "bidirectional"))
    )
    (net (code "58") (name "Net-(2D2G-VCC)") (class "Default")
      (node (ref "2C1") (pin "1") (pinfunction "1_1") (pintype "passive"))
      (node (ref "2D2") (pin "14") (pinfunction "VCC_14") (pintype "power_in"))
      (node (ref "D92") (pin "C") (pinfunction "C_C") (pintype "passive"))
    )
    (net (code "59") (name "Net-(D49-PadA)") (class "Default")
      (node (ref "D49") (pin "A") (pinfunction "A_A") (pintype "passive"))
      (node (ref "JB47") (pin "1") (pinfunction "1_1") (pintype "passive"))
    )
    (net (code "60") (name "Net-(D50-PadA)") (class "Default")
      (node (ref "D50") (pin "A") (pinfunction "A_A") (pintype "passive"))
      (node (ref "JB48") (pin "1") (pinfunction "1_1") (pintype "passive"))
    )
    (net (code "61") (name "Net-(D51-PadA)") (class "Default")
      (node (ref "D51") (pin "A") (pinfunction "A_A") (pintype "passive"))
      (node (ref "JB49") (pin "1") (pinfunction "1_1") (pintype "passive"))
    )
    (net (code "62") (name "Net-(D52-PadA)") (class "Default")
      (node (ref "D52") (pin "A") (pinfunction "A_A") (pintype "passive"))
      (node (ref "JB50") (pin "1") (pinfunction "1_1") (pintype "passive"))
    )
    (net (code "63") (name "Net-(D53-PadA)") (class "Default")
      (node (ref "D53") (pin "A") (pinfunction "A_A") (pintype "passive"))
      (node (ref "JB51") (pin "1") (pinfunction "1_1") (pintype "passive"))
    )
    (net (code "64") (name "Net-(D54-PadA)") (class "Default")
      (node (ref "D54") (pin "A") (pinfunction "A_A") (pintype "passive"))
      (node (ref "JB52") (pin "1") (pinfunction "1_1") (pintype "passive"))
    )
    (net (code "65") (name "Net-(D55-PadA)") (class "Default")
      (node (ref "D55") (pin "A") (pinfunction "A_A") (pintype "passive"))
      (node (ref "JB53") (pin "1") (pinfunction "1_1") (pintype "passive"))
    )
    (net (code "66") (name "Net-(D56-PadA)") (class "Default")
      (node (ref "D56") (pin "A") (pinfunction "A_A") (pintype "passive"))
      (node (ref "JB54") (pin "1") (pinfunction "1_1") (pintype "passive"))
    )
    (net (code "67") (name "Net-(D57-PadA)") (class "Default")
      (node (ref "D57") (pin "A") (pinfunction "A_A") (pintype "passive"))
      (node (ref "JB55") (pin "1") (pinfunction "1_1") (pintype "passive"))
    )
    (net (code "68") (name "Net-(D58-PadA)") (class "Default")
      (node (ref "D58") (pin "A") (pinfunction "A_A") (pintype "passive"))
      (node (ref "JB56") (pin "1") (pinfunction "1_1") (pintype "passive"))
    )
    (net (code "69") (name "Net-(D59-PadA)") (class "Default")
      (node (ref "D59") (pin "A") (pinfunction "A_A") (pintype "passive"))
      (node (ref "JB57") (pin "1") (pinfunction "1_1") (pintype "passive"))
    )
    (net (code "70") (name "Net-(D60-PadA)") (class "Default")
      (node (ref "D60") (pin "A") (pinfunction "A_A") (pintype "passive"))
      (node (ref "JB58") (pin "1") (pinfunction "1_1") (pintype "passive"))
    )
    (net (code "71") (name "Net-(D61-PadA)") (class "Default")
      (node (ref "D61") (pin "A") (pinfunction "A_A") (pintype "passive"))
      (node (ref "JB59") (pin "1") (pinfunction "1_1") (pintype "passive"))
    )
    (net (code "72") (name "Net-(D62-PadA)") (class "Default")
      (node (ref "D62") (pin "A") (pinfunction "A_A") (pintype "passive"))
      (node (ref "JB60") (pin "1") (pinfunction "1_1") (pintype "passive"))
    )
    (net (code "73") (name "Net-(D63-PadA)") (class "Default")
      (node (ref "D63") (pin "A") (pinfunction "A_A") (pintype "passive"))
      (node (ref "JB61") (pin "1") (pinfunction "1_1") (pintype "passive"))
    )
    (net (code "74") (name "Net-(D64-PadA)") (class "Default")
      (node (ref "D64") (pin "A") (pinfunction "A_A") (pintype "passive"))
      (node (ref "JB62") (pin "1") (pinfunction "1_1") (pintype "passive"))
    )
    (net (code "75") (name "Net-(D64B-PadA)") (class "Default")
      (node (ref "D64B") (pin "A") (pinfunction "A_A") (pintype "passive"))
      (node (ref "JB74B") (pin "1") (pinfunction "1_1") (pintype "passive"))
    )
    (net (code "76") (name "Net-(D65-PadA)") (class "Default")
      (node (ref "D65") (pin "A") (pinfunction "A_A") (pintype "passive"))
      (node (ref "JB63") (pin "1") (pinfunction "1_1") (pintype "passive"))
    )
    (net (code "77") (name "Net-(D66-PadA)") (class "Default")
      (node (ref "D66") (pin "A") (pinfunction "A_A") (pintype "passive"))
      (node (ref "JB64") (pin "1") (pinfunction "1_1") (pintype "passive"))
    )
    (net (code "78") (name "Net-(D67-PadA)") (class "Default")
      (node (ref "D67") (pin "A") (pinfunction "A_A") (pintype "passive"))
      (node (ref "JB65") (pin "1") (pinfunction "1_1") (pintype "passive"))
    )
    (net (code "79") (name "Net-(D67B-PadA)") (class "Default")
      (node (ref "D67B") (pin "A") (pinfunction "A_A") (pintype "passive"))
      (node (ref "JB67B") (pin "1") (pinfunction "1_1") (pintype "passive"))
    )
    (net (code "80") (name "Net-(D68-PadA)") (class "Default")
      (node (ref "D68") (pin "A") (pinfunction "A_A") (pintype "passive"))
      (node (ref "JB66") (pin "1") (pinfunction "1_1") (pintype "passive"))
    )
    (net (code "81") (name "Net-(D69-PadA)") (class "Default")
      (node (ref "D69") (pin "A") (pinfunction "A_A") (pintype "passive"))
      (node (ref "JB67") (pin "1") (pinfunction "1_1") (pintype "passive"))
    )
    (net (code "82") (name "Net-(D70-PadA)") (class "Default")
      (node (ref "D70") (pin "A") (pinfunction "A_A") (pintype "passive"))
      (node (ref "JB68") (pin "1") (pinfunction "1_1") (pintype "passive"))
    )
    (net (code "83") (name "Net-(D71-PadA)") (class "Default")
      (node (ref "D71") (pin "A") (pinfunction "A_A") (pintype "passive"))
      (node (ref "JB69") (pin "1") (pinfunction "1_1") (pintype "passive"))
    )
    (net (code "84") (name "Net-(D72-PadA)") (class "Default")
      (node (ref "D72") (pin "A") (pinfunction "A_A") (pintype "passive"))
      (node (ref "JB70") (pin "1") (pinfunction "1_1") (pintype "passive"))
    )
    (net (code "85") (name "Net-(D73-PadA)") (class "Default")
      (node (ref "D73") (pin "A") (pinfunction "A_A") (pintype "passive"))
      (node (ref "JB71") (pin "1") (pinfunction "1_1") (pintype "passive"))
    )
    (net (code "86") (name "Net-(D74-PadA)") (class "Default")
      (node (ref "D74") (pin "A") (pinfunction "A_A") (pintype "passive"))
      (node (ref "JB72") (pin "1") (pinfunction "1_1") (pintype "passive"))
    )
    (net (code "87") (name "Net-(D75-PadA)") (class "Default")
      (node (ref "D75") (pin "A") (pinfunction "A_A") (pintype "passive"))
      (node (ref "JB73") (pin "1") (pinfunction "1_1") (pintype "passive"))
    )
    (net (code "88") (name "Net-(D76-PadA)") (class "Default")
      (node (ref "D76") (pin "A") (pinfunction "A_A") (pintype "passive"))
      (node (ref "JA74") (pin "2") (pinfunction "2_2") (pintype "passive"))
    )
    (net (code "89") (name "Net-(D77-PadA)") (class "Default")
      (node (ref "D77") (pin "A") (pinfunction "A_A") (pintype "passive"))
      (node (ref "JB75") (pin "1") (pinfunction "1_1") (pintype "passive"))
    )
    (net (code "90") (name "Net-(D78-PadA)") (class "Default")
      (node (ref "D78") (pin "A") (pinfunction "A_A") (pintype "passive"))
      (node (ref "JB76") (pin "1") (pinfunction "1_1") (pintype "passive"))
    )
    (net (code "91") (name "Net-(D79-PadA)") (class "Default")
      (node (ref "D79") (pin "A") (pinfunction "A_A") (pintype "passive"))
      (node (ref "JB77") (pin "1") (pinfunction "1_1") (pintype "passive"))
    )
    (net (code "92") (name "Net-(D80-PadA)") (class "Default")
      (node (ref "D80") (pin "A") (pinfunction "A_A") (pintype "passive"))
      (node (ref "JB78") (pin "1") (pinfunction "1_1") (pintype "passive"))
    )
    (net (code "93") (name "Net-(D81-PadA)") (class "Default")
      (node (ref "D81") (pin "A") (pinfunction "A_A") (pintype "passive"))
      (node (ref "JB79") (pin "1") (pinfunction "1_1") (pintype "passive"))
    )
    (net (code "94") (name "Net-(D82-PadA)") (class "Default")
      (node (ref "D82") (pin "A") (pinfunction "A_A") (pintype "passive"))
      (node (ref "JB80") (pin "1") (pinfunction "1_1") (pintype "passive"))
    )
    (net (code "95") (name "Net-(D83-PadA)") (class "Default")
      (node (ref "D83") (pin "A") (pinfunction "A_A") (pintype "passive"))
      (node (ref "JB81") (pin "1") (pinfunction "1_1") (pintype "passive"))
    )
    (net (code "96") (name "Net-(D84-PadA)") (class "Default")
      (node (ref "D84") (pin "A") (pinfunction "A_A") (pintype "passive"))
      (node (ref "JB82") (pin "1") (pinfunction "1_1") (pintype "passive"))
    )
    (net (code "97") (name "Net-(D85-PadA)") (class "Default")
      (node (ref "D85") (pin "A") (pinfunction "A_A") (pintype "passive"))
      (node (ref "JB83") (pin "1") (pinfunction "1_1") (pintype "passive"))
    )
    (net (code "98") (name "Net-(D86-PadA)") (class "Default")
      (node (ref "D86") (pin "A") (pinfunction "A_A") (pintype "passive"))
      (node (ref "JB84") (pin "1") (pinfunction "1_1") (pintype "passive"))
    )
    (net (code "99") (name "Net-(D87-PadA)") (class "Default")
      (node (ref "D87") (pin "A") (pinfunction "A_A") (pintype "passive"))
      (node (ref "JB85") (pin "1") (pinfunction "1_1") (pintype "passive"))
    )
    (net (code "100") (name "Net-(D88-PadA)") (class "Default")
      (node (ref "D88") (pin "A") (pinfunction "A_A") (pintype "passive"))
      (node (ref "JB86") (pin "1") (pinfunction "1_1") (pintype "passive"))
    )
    (net (code "101") (name "Net-(D89-PadA)") (class "Default")
      (node (ref "D89") (pin "A") (pinfunction "A_A") (pintype "passive"))
      (node (ref "JB87") (pin "1") (pinfunction "1_1") (pintype "passive"))
    )
    (net (code "102") (name "Net-(D92-PadA)") (class "Default")
      (node (ref "D92") (pin "A") (pinfunction "A_A") (pintype "passive"))
      (node (ref "D93") (pin "C") (pinfunction "C_C") (pintype "passive"))
    )
    (net (code "103") (name "Net-(J46-P$1)") (class "Default")
      (node (ref "J46") (pin "1") (pinfunction "P$1_1") (pintype "bidirectional"))
      (node (ref "J95") (pin "2") (pinfunction "P$2_2") (pintype "bidirectional"))
    )
    (net (code "104") (name "Net-(J48-P$1)") (class "Default")
      (node (ref "J48") (pin "1") (pinfunction "P$1_1") (pintype "bidirectional"))
      (node (ref "J49") (pin "2") (pinfunction "P$2_2") (pintype "bidirectional"))
    )
    (net (code "105") (name "Net-(J57-P$1)") (class "Default")
      (node (ref "J57") (pin "1") (pinfunction "P$1_1") (pintype "bidirectional"))
      (node (ref "J58") (pin "2") (pinfunction "P$2_2") (pintype "bidirectional"))
    )
    (net (code "106") (name "Net-(J59-P$1)") (class "Default")
      (node (ref "J59") (pin "1") (pinfunction "P$1_1") (pintype "bidirectional"))
      (node (ref "J60") (pin "2") (pinfunction "P$2_2") (pintype "bidirectional"))
    )
    (net (code "107") (name "Net-(J61-P$2)") (class "Default")
      (node (ref "J61") (pin "2") (pinfunction "P$2_2") (pintype "bidirectional"))
      (node (ref "J62") (pin "1") (pinfunction "P$1_1") (pintype "bidirectional"))
    )
    (net (code "108") (name "Net-(J64-P$1)") (class "Default")
      (node (ref "J64") (pin "1") (pinfunction "P$1_1") (pintype "bidirectional"))
      (node (ref "SV4") (pin "4") (pinfunction "4_4") (pintype "passive"))
    )
    (net (code "109") (name "Net-(J65-P$1)") (class "Default")
      (node (ref "J65") (pin "1") (pinfunction "P$1_1") (pintype "bidirectional"))
      (node (ref "SV4") (pin "3") (pinfunction "3_3") (pintype "passive"))
    )
    (net (code "110") (name "Net-(J65-P$2)") (class "Default")
      (node (ref "J65") (pin "2") (pinfunction "P$2_2") (pintype "bidirectional"))
      (node (ref "J66") (pin "1") (pinfunction "P$1_1") (pintype "bidirectional"))
    )
    (net (code "111") (name "Net-(J67-P$1)") (class "Default")
      (node (ref "J67") (pin "1") (pinfunction "P$1_1") (pintype "bidirectional"))
      (node (ref "SV4") (pin "2") (pinfunction "2_2") (pintype "passive"))
    )
    (net (code "112") (name "Net-(J67-P$2)") (class "Default")
      (node (ref "J67") (pin "2") (pinfunction "P$2_2") (pintype "bidirectional"))
      (node (ref "J68") (pin "1") (pinfunction "P$1_1") (pintype "bidirectional"))
    )
    (net (code "113") (name "Net-(J68-P$2)") (class "Default")
      (node (ref "J68") (pin "2") (pinfunction "P$2_2") (pintype "bidirectional"))
      (node (ref "J69") (pin "1") (pinfunction "P$1_1") (pintype "bidirectional"))
    )
    (net (code "114") (name "Net-(J70-P$1)") (class "Default")
      (node (ref "J70") (pin "1") (pinfunction "P$1_1") (pintype "bidirectional"))
      (node (ref "J73") (pin "2") (pinfunction "P$2_2") (pintype "bidirectional"))
    )
    (net (code "115") (name "Net-(J71-P$1)") (class "Default")
      (node (ref "J71") (pin "1") (pinfunction "P$1_1") (pintype "bidirectional"))
      (node (ref "J74") (pin "2") (pinfunction "P$2_2") (pintype "bidirectional"))
    )
    (net (code "116") (name "Net-(J72-P$1)") (class "Default")
      (node (ref "J72") (pin "1") (pinfunction "P$1_1") (pintype "bidirectional"))
      (node (ref "J75") (pin "2") (pinfunction "P$2_2") (pintype "bidirectional"))
    )
    (net (code "117") (name "Net-(J73-P$1)") (class "Default")
      (node (ref "J73") (pin "1") (pinfunction "P$1_1") (pintype "bidirectional"))
      (node (ref "J77") (pin "2") (pinfunction "P$2_2") (pintype "bidirectional"))
    )
    (net (code "118") (name "Net-(J74-P$1)") (class "Default")
      (node (ref "J74") (pin "1") (pinfunction "P$1_1") (pintype "bidirectional"))
      (node (ref "J78") (pin "2") (pinfunction "P$2_2") (pintype "bidirectional"))
    )
    (net (code "119") (name "Net-(J75-P$1)") (class "Default")
      (node (ref "J75") (pin "1") (pinfunction "P$1_1") (pintype "bidirectional"))
      (node (ref "J79") (pin "2") (pinfunction "P$2_2") (pintype "bidirectional"))
    )
    (net (code "120") (name "Net-(J77-P$1)") (class "Default")
      (node (ref "J77") (pin "1") (pinfunction "P$1_1") (pintype "bidirectional"))
      (node (ref "J81") (pin "2") (pinfunction "P$2_2") (pintype "bidirectional"))
    )
    (net (code "121") (name "Net-(J78-P$1)") (class "Default")
      (node (ref "J78") (pin "1") (pinfunction "P$1_1") (pintype "bidirectional"))
      (node (ref "J82") (pin "2") (pinfunction "P$2_2") (pintype "bidirectional"))
    )
    (net (code "122") (name "Net-(J79-P$1)") (class "Default")
      (node (ref "J79") (pin "1") (pinfunction "P$1_1") (pintype "bidirectional"))
      (node (ref "J80") (pin "2") (pinfunction "P$2_2") (pintype "bidirectional"))
    )
    (net (code "123") (name "Net-(J84-P$1)") (class "Default")
      (node (ref "J84") (pin "1") (pinfunction "P$1_1") (pintype "bidirectional"))
      (node (ref "J85") (pin "2") (pinfunction "P$2_2") (pintype "bidirectional"))
    )
    (net (code "124") (name "Net-(J85-P$1)") (class "Default")
      (node (ref "J85") (pin "1") (pinfunction "P$1_1") (pintype "bidirectional"))
      (node (ref "JA59") (pin "2") (pinfunction "2_2") (pintype "passive"))
      (node (ref "JA67") (pin "2") (pinfunction "2_2") (pintype "passive"))
      (node (ref "JA67B") (pin "2") (pinfunction "2_2") (pintype "passive"))
      (node (ref "JA81") (pin "2") (pinfunction "2_2") (pintype "passive"))
      (node (ref "JA85") (pin "2") (pinfunction "2_2") (pintype "passive"))
      (node (ref "JA86") (pin "2") (pinfunction "2_2") (pintype "passive"))
      (node (ref "JB74") (pin "1") (pinfunction "1_1") (pintype "passive"))
    )
    (net (code "125") (name "Net-(J86-P$1)") (class "Default")
      (node (ref "2C2") (pin "1") (pinfunction "1_1") (pintype "passive"))
      (node (ref "J86") (pin "1") (pinfunction "P$1_1") (pintype "bidirectional"))
      (node (ref "R16") (pin "1") (pinfunction "1_1") (pintype "passive"))
    )
    (net (code "126") (name "Net-(J89-P$2)") (class "Default")
      (node (ref "J89") (pin "2") (pinfunction "P$2_2") (pintype "bidirectional"))
      (node (ref "J92") (pin "1") (pinfunction "P$1_1") (pintype "bidirectional"))
    )
    (net (code "127") (name "Net-(J90-P$1)") (class "Default")
      (node (ref "J90") (pin "1") (pinfunction "P$1_1") (pintype "bidirectional"))
      (node (ref "J91") (pin "2") (pinfunction "P$2_2") (pintype "bidirectional"))
    )
    (net (code "128") (name "Net-(S47A-PIN-1)") (class "Default")
      (node (ref "JB47") (pin "2") (pinfunction "2_2") (pintype "passive"))
      (node (ref "S47") (pin "SW1") (pinfunction "PIN-1_SW1") (pintype "passive"))
    )
    (net (code "129") (name "Net-(S47A-PIN-2)") (class "Default")
      (node (ref "JA47") (pin "1") (pinfunction "1_1") (pintype "passive"))
      (node (ref "S47") (pin "SW2") (pinfunction "PIN-2_SW2") (pintype "passive"))
    )
    (net (code "130") (name "Net-(S48A-PIN-1)") (class "Default")
      (node (ref "JB48") (pin "2") (pinfunction "2_2") (pintype "passive"))
      (node (ref "S48") (pin "SW1") (pinfunction "PIN-1_SW1") (pintype "passive"))
    )
    (net (code "131") (name "Net-(S48A-PIN-2)") (class "Default")
      (node (ref "JA48") (pin "1") (pinfunction "1_1") (pintype "passive"))
      (node (ref "S48") (pin "SW2") (pinfunction "PIN-2_SW2") (pintype "passive"))
    )
    (net (code "132") (name "Net-(S49A-PIN-1)") (class "Default")
      (node (ref "JB49") (pin "2") (pinfunction "2_2") (pintype "passive"))
      (node (ref "S49") (pin "SW1") (pinfunction "PIN-1_SW1") (pintype "passive"))
    )
    (net (code "133") (name "Net-(S49A-PIN-2)") (class "Default")
      (node (ref "JA49") (pin "1") (pinfunction "1_1") (pintype "passive"))
      (node (ref "S49") (pin "SW2") (pinfunction "PIN-2_SW2") (pintype "passive"))
    )
    (net (code "134") (name "Net-(S50A-PIN-1)") (class "Default")
      (node (ref "JA50") (pin "1") (pinfunction "1_1") (pintype "passive"))
      (node (ref "S50") (pin "SW1") (pinfunction "PIN-1_SW1") (pintype "passive"))
    )
    (net (code "135") (name "Net-(S50A-PIN-2)") (class "Default")
      (node (ref "JB50") (pin "2") (pinfunction "2_2") (pintype "passive"))
      (node (ref "S50") (pin "SW2") (pinfunction "PIN-2_SW2") (pintype "passive"))
    )
    (net (code "136") (name "Net-(S51A-PIN-1)") (class "Default")
      (node (ref "JB51") (pin "2") (pinfunction "2_2") (pintype "passive"))
      (node (ref "S51") (pin "SW1") (pinfunction "PIN-1_SW1") (pintype "passive"))
    )
    (net (code "137") (name "Net-(S51A-PIN-2)") (class "Default")
      (node (ref "JA51") (pin "1") (pinfunction "1_1") (pintype "passive"))
      (node (ref "S51") (pin "SW2") (pinfunction "PIN-2_SW2") (pintype "passive"))
    )
    (net (code "138") (name "Net-(S52A-PIN-1)") (class "Default")
      (node (ref "JB52") (pin "2") (pinfunction "2_2") (pintype "passive"))
      (node (ref "S52") (pin "SW1") (pinfunction "PIN-1_SW1") (pintype "passive"))
    )
    (net (code "139") (name "Net-(S52A-PIN-2)") (class "Default")
      (node (ref "JA52") (pin "1") (pinfunction "1_1") (pintype "passive"))
      (node (ref "S52") (pin "SW2") (pinfunction "PIN-2_SW2") (pintype "passive"))
    )
    (net (code "140") (name "Net-(S53A-PIN-1)") (class "Default")
      (node (ref "JB53") (pin "2") (pinfunction "2_2") (pintype "passive"))
      (node (ref "S53") (pin "SW1") (pinfunction "PIN-1_SW1") (pintype "passive"))
    )
    (net (code "141") (name "Net-(S53A-PIN-2)") (class "Default")
      (node (ref "JA53") (pin "1") (pinfunction "1_1") (pintype "passive"))
      (node (ref "S53") (pin "SW2") (pinfunction "PIN-2_SW2") (pintype "passive"))
    )
    (net (code "142") (name "Net-(S54A-PIN-1)") (class "Default")
      (node (ref "JB54") (pin "2") (pinfunction "2_2") (pintype "passive"))
      (node (ref "S54") (pin "SW1") (pinfunction "PIN-1_SW1") (pintype "passive"))
    )
    (net (code "143") (name "Net-(S54A-PIN-2)") (class "Default")
      (node (ref "JA54") (pin "1") (pinfunction "1_1") (pintype "passive"))
      (node (ref "S54") (pin "SW2") (pinfunction "PIN-2_SW2") (pintype "passive"))
    )
    (net (code "144") (name "Net-(S55A-PIN-1)") (class "Default")
      (node (ref "JB55") (pin "2") (pinfunction "2_2") (pintype "passive"))
      (node (ref "S55") (pin "SW1") (pinfunction "PIN-1_SW1") (pintype "passive"))
    )
    (net (code "145") (name "Net-(S55A-PIN-2)") (class "Default")
      (node (ref "JA55") (pin "1") (pinfunction "1_1") (pintype "passive"))
      (node (ref "S55") (pin "SW2") (pinfunction "PIN-2_SW2") (pintype "passive"))
    )
    (net (code "146") (name "Net-(S56A-PIN-1)") (class "Default")
      (node (ref "JB56") (pin "2") (pinfunction "2_2") (pintype "passive"))
      (node (ref "S56") (pin "SW1") (pinfunction "PIN-1_SW1") (pintype "passive"))
    )
    (net (code "147") (name "Net-(S56A-PIN-2)") (class "Default")
      (node (ref "JA56") (pin "1") (pinfunction "1_1") (pintype "passive"))
      (node (ref "S56") (pin "SW2") (pinfunction "PIN-2_SW2") (pintype "passive"))
    )
    (net (code "148") (name "Net-(S57A-PIN-1)") (class "Default")
      (node (ref "JA57") (pin "1") (pinfunction "1_1") (pintype "passive"))
      (node (ref "S57") (pin "SW1") (pinfunction "PIN-1_SW1") (pintype "passive"))
    )
    (net (code "149") (name "Net-(S57A-PIN-2)") (class "Default")
      (node (ref "JB57") (pin "2") (pinfunction "2_2") (pintype "passive"))
      (node (ref "S57") (pin "SW2") (pinfunction "PIN-2_SW2") (pintype "passive"))
    )
    (net (code "150") (name "Net-(S58A-PIN-1)") (class "Default")
      (node (ref "JA58") (pin "1") (pinfunction "1_1") (pintype "passive"))
      (node (ref "S58") (pin "SW1") (pinfunction "PIN-1_SW1") (pintype "passive"))
    )
    (net (code "151") (name "Net-(S58A-PIN-2)") (class "Default")
      (node (ref "JB58") (pin "2") (pinfunction "2_2") (pintype "passive"))
      (node (ref "S58") (pin "SW2") (pinfunction "PIN-2_SW2") (pintype "passive"))
    )
    (net (code "152") (name "Net-(S59A-PIN-1)") (class "Default")
      (node (ref "JA59") (pin "1") (pinfunction "1_1") (pintype "passive"))
      (node (ref "S59") (pin "SW1") (pinfunction "PIN-1_SW1") (pintype "passive"))
    )
    (net (code "153") (name "Net-(S59A-PIN-2)") (class "Default")
      (node (ref "JB59") (pin "2") (pinfunction "2_2") (pintype "passive"))
      (node (ref "S59") (pin "SW2") (pinfunction "PIN-2_SW2") (pintype "passive"))
    )
    (net (code "154") (name "Net-(S60A-PIN-1)") (class "Default")
      (node (ref "JB60") (pin "2") (pinfunction "2_2") (pintype "passive"))
      (node (ref "S60") (pin "SW1") (pinfunction "PIN-1_SW1") (pintype "passive"))
    )
    (net (code "155") (name "Net-(S60A-PIN-2)") (class "Default")
      (node (ref "JA60") (pin "1") (pinfunction "1_1") (pintype "passive"))
      (node (ref "S60") (pin "SW2") (pinfunction "PIN-2_SW2") (pintype "passive"))
    )
    (net (code "156") (name "Net-(S61A-PIN-1)") (class "Default")
      (node (ref "JB61") (pin "2") (pinfunction "2_2") (pintype "passive"))
      (node (ref "S61") (pin "SW1") (pinfunction "PIN-1_SW1") (pintype "passive"))
    )
    (net (code "157") (name "Net-(S61A-PIN-2)") (class "Default")
      (node (ref "JA61") (pin "1") (pinfunction "1_1") (pintype "passive"))
      (node (ref "S61") (pin "SW2") (pinfunction "PIN-2_SW2") (pintype "passive"))
    )
    (net (code "158") (name "Net-(S62A-PIN-1)") (class "Default")
      (node (ref "JA62") (pin "1") (pinfunction "1_1") (pintype "passive"))
      (node (ref "S62") (pin "SW1") (pinfunction "PIN-1_SW1") (pintype "passive"))
    )
    (net (code "159") (name "Net-(S62A-PIN-2)") (class "Default")
      (node (ref "JB62") (pin "2") (pinfunction "2_2") (pintype "passive"))
      (node (ref "S62") (pin "SW2") (pinfunction "PIN-2_SW2") (pintype "passive"))
    )
    (net (code "160") (name "Net-(S63A-PIN-1)") (class "Default")
      (node (ref "JB63") (pin "2") (pinfunction "2_2") (pintype "passive"))
      (node (ref "S63") (pin "SW1") (pinfunction "PIN-1_SW1") (pintype "passive"))
    )
    (net (code "161") (name "Net-(S63A-PIN-2)") (class "Default")
      (node (ref "JA63") (pin "1") (pinfunction "1_1") (pintype "passive"))
      (node (ref "S63") (pin "SW2") (pinfunction "PIN-2_SW2") (pintype "passive"))
    )
    (net (code "162") (name "Net-(S64A-PIN-1)") (class "Default")
      (node (ref "JA64") (pin "1") (pinfunction "1_1") (pintype "passive"))
      (node (ref "S64") (pin "SW1") (pinfunction "PIN-1_SW1") (pintype "passive"))
    )
    (net (code "163") (name "Net-(S64A-PIN-2)") (class "Default")
      (node (ref "JB64") (pin "2") (pinfunction "2_2") (pintype "passive"))
      (node (ref "S64") (pin "SW2") (pinfunction "PIN-2_SW2") (pintype "passive"))
    )
    (net (code "164") (name "Net-(S65A-PIN-1)") (class "Default")
      (node (ref "JA65") (pin "1") (pinfunction "1_1") (pintype "passive"))
      (node (ref "S65") (pin "SW1") (pinfunction "PIN-1_SW1") (pintype "passive"))
    )
    (net (code "165") (name "Net-(S65A-PIN-2)") (class "Default")
      (node (ref "JB65") (pin "2") (pinfunction "2_2") (pintype "passive"))
      (node (ref "S65") (pin "SW2") (pinfunction "PIN-2_SW2") (pintype "passive"))
    )
    (net (code "166") (name "Net-(S66A-PIN-1)") (class "Default")
      (node (ref "JB66") (pin "2") (pinfunction "2_2") (pintype "passive"))
      (node (ref "S66") (pin "SW1") (pinfunction "PIN-1_SW1") (pintype "passive"))
    )
    (net (code "167") (name "Net-(S66A-PIN-2)") (class "Default")
      (node (ref "JA66") (pin "1") (pinfunction "1_1") (pintype "passive"))
      (node (ref "S66") (pin "SW2") (pinfunction "PIN-2_SW2") (pintype "passive"))
    )
    (net (code "168") (name "Net-(S67A-PIN-1)") (class "Default")
      (node (ref "JA67") (pin "1") (pinfunction "1_1") (pintype "passive"))
      (node (ref "S67") (pin "SW1") (pinfunction "PIN-1_SW1") (pintype "passive"))
    )
    (net (code "169") (name "Net-(S67A-PIN-2)") (class "Default")
      (node (ref "JB67") (pin "2") (pinfunction "2_2") (pintype "passive"))
      (node (ref "S67") (pin "SW2") (pinfunction "PIN-2_SW2") (pintype "passive"))
    )
    (net (code "170") (name "Net-(S67CA-PIN-1)") (class "Default")
      (node (ref "JA67B") (pin "1") (pinfunction "1_1") (pintype "passive"))
      (node (ref "S67C") (pin "SW1") (pinfunction "PIN-1_SW1") (pintype "passive"))
    )
    (net (code "171") (name "Net-(S67CA-PIN-2)") (class "Default")
      (node (ref "JB67B") (pin "2") (pinfunction "2_2") (pintype "passive"))
      (node (ref "S67C") (pin "SW2") (pinfunction "PIN-2_SW2") (pintype "passive"))
    )
    (net (code "172") (name "Net-(S68A-PIN-1)") (class "Default")
      (node (ref "JB68") (pin "2") (pinfunction "2_2") (pintype "passive"))
      (node (ref "S68") (pin "SW1") (pinfunction "PIN-1_SW1") (pintype "passive"))
    )
    (net (code "173") (name "Net-(S68A-PIN-2)") (class "Default")
      (node (ref "JA68") (pin "1") (pinfunction "1_1") (pintype "passive"))
      (node (ref "S68") (pin "SW2") (pinfunction "PIN-2_SW2") (pintype "passive"))
    )
    (net (code "174") (name "Net-(S69A-PIN-1)") (class "Default")
      (node (ref "JB69") (pin "2") (pinfunction "2_2") (pintype "passive"))
      (node (ref "S69") (pin "SW1") (pinfunction "PIN-1_SW1") (pintype "passive"))
    )
    (net (code "175") (name "Net-(S69A-PIN-2)") (class "Default")
      (node (ref "JA69") (pin "1") (pinfunction "1_1") (pintype "passive"))
      (node (ref "S69") (pin "SW2") (pinfunction "PIN-2_SW2") (pintype "passive"))
    )
    (net (code "176") (name "Net-(S70A-PIN-1)") (class "Default")
      (node (ref "JB70") (pin "2") (pinfunction "2_2") (pintype "passive"))
      (node (ref "S70") (pin "SW1") (pinfunction "PIN-1_SW1") (pintype "passive"))
    )
    (net (code "177") (name "Net-(S70A-PIN-2)") (class "Default")
      (node (ref "JA70") (pin "1") (pinfunction "1_1") (pintype "passive"))
      (node (ref "S70") (pin "SW2") (pinfunction "PIN-2_SW2") (pintype "passive"))
    )
    (net (code "178") (name "Net-(S71A-PIN-1)") (class "Default")
      (node (ref "JB71") (pin "2") (pinfunction "2_2") (pintype "passive"))
      (node (ref "S71") (pin "SW1") (pinfunction "PIN-1_SW1") (pintype "passive"))
    )
    (net (code "179") (name "Net-(S71A-PIN-2)") (class "Default")
      (node (ref "JA71") (pin "1") (pinfunction "1_1") (pintype "passive"))
      (node (ref "S71") (pin "SW2") (pinfunction "PIN-2_SW2") (pintype "passive"))
    )
    (net (code "180") (name "Net-(S72A-PIN-1)") (class "Default")
      (node (ref "JA72") (pin "1") (pinfunction "1_1") (pintype "passive"))
      (node (ref "S72") (pin "SW1") (pinfunction "PIN-1_SW1") (pintype "passive"))
    )
    (net (code "181") (name "Net-(S72A-PIN-2)") (class "Default")
      (node (ref "JB72") (pin "2") (pinfunction "2_2") (pintype "passive"))
      (node (ref "S72") (pin "SW2") (pinfunction "PIN-2_SW2") (pintype "passive"))
    )
    (net (code "182") (name "Net-(S73A-PIN-1)") (class "Default")
      (node (ref "JA73") (pin "1") (pinfunction "1_1") (pintype "passive"))
      (node (ref "S73") (pin "SW1") (pinfunction "PIN-1_SW1") (pintype "passive"))
    )
    (net (code "183") (name "Net-(S73A-PIN-2)") (class "Default")
      (node (ref "JB73") (pin "2") (pinfunction "2_2") (pintype "passive"))
      (node (ref "S73") (pin "SW2") (pinfunction "PIN-2_SW2") (pintype "passive"))
    )
    (net (code "184") (name "Net-(S74A-PIN-1)") (class "Default")
      (node (ref "JA74B") (pin "1") (pinfunction "1_1") (pintype "passive"))
      (node (ref "S74") (pin "SW1") (pinfunction "PIN-1_SW1") (pintype "passive"))
    )
    (net (code "185") (name "Net-(S74A-PIN-2)") (class "Default")
      (node (ref "JB74B") (pin "2") (pinfunction "2_2") (pintype "passive"))
      (node (ref "S74") (pin "SW2") (pinfunction "PIN-2_SW2") (pintype "passive"))
    )
    (net (code "186") (name "Net-(S74AA-PIN-1)") (class "Default")
      (node (ref "JB74") (pin "2") (pinfunction "2_2") (pintype "passive"))
      (node (ref "S74A") (pin "SW1") (pinfunction "PIN-1_SW1") (pintype "passive"))
    )
    (net (code "187") (name "Net-(S74AA-PIN-2)") (class "Default")
      (node (ref "JA74") (pin "1") (pinfunction "1_1") (pintype "passive"))
      (node (ref "S74A") (pin "SW2") (pinfunction "PIN-2_SW2") (pintype "passive"))
    )
    (net (code "188") (name "Net-(S75A-PIN-1)") (class "Default")
      (node (ref "JB75") (pin "2") (pinfunction "2_2") (pintype "passive"))
      (node (ref "S75") (pin "SW1") (pinfunction "PIN-1_SW1") (pintype "passive"))
    )
    (net (code "189") (name "Net-(S75A-PIN-2)") (class "Default")
      (node (ref "JA75") (pin "1") (pinfunction "1_1") (pintype "passive"))
      (node (ref "S75") (pin "SW2") (pinfunction "PIN-2_SW2") (pintype "passive"))
    )
    (net (code "190") (name "Net-(S76A-PIN-1)") (class "Default")
      (node (ref "JA76") (pin "1") (pinfunction "1_1") (pintype "passive"))
      (node (ref "S76") (pin "SW1") (pinfunction "PIN-1_SW1") (pintype "passive"))
    )
    (net (code "191") (name "Net-(S76A-PIN-2)") (class "Default")
      (node (ref "JB76") (pin "2") (pinfunction "2_2") (pintype "passive"))
      (node (ref "S76") (pin "SW2") (pinfunction "PIN-2_SW2") (pintype "passive"))
    )
    (net (code "192") (name "Net-(S77A-PIN-1)") (class "Default")
      (node (ref "JB77") (pin "2") (pinfunction "2_2") (pintype "passive"))
      (node (ref "S77") (pin "SW1") (pinfunction "PIN-1_SW1") (pintype "passive"))
    )
    (net (code "193") (name "Net-(S77A-PIN-2)") (class "Default")
      (node (ref "JA77") (pin "1") (pinfunction "1_1") (pintype "passive"))
      (node (ref "S77") (pin "SW2") (pinfunction "PIN-2_SW2") (pintype "passive"))
    )
    (net (code "194") (name "Net-(S78A-PIN-1)") (class "Default")
      (node (ref "JA78") (pin "1") (pinfunction "1_1") (pintype "passive"))
      (node (ref "S78") (pin "SW1") (pinfunction "PIN-1_SW1") (pintype "passive"))
    )
    (net (code "195") (name "Net-(S78A-PIN-2)") (class "Default")
      (node (ref "JB78") (pin "2") (pinfunction "2_2") (pintype "passive"))
      (node (ref "S78") (pin "SW2") (pinfunction "PIN-2_SW2") (pintype "passive"))
    )
    (net (code "196") (name "Net-(S79A-PIN-1)") (class "Default")
      (node (ref "JA79") (pin "1") (pinfunction "1_1") (pintype "passive"))
      (node (ref "S79") (pin "SW1") (pinfunction "PIN-1_SW1") (pintype "passive"))
    )
    (net (code "197") (name "Net-(S79A-PIN-2)") (class "Default")
      (node (ref "JB79") (pin "2") (pinfunction "2_2") (pintype "passive"))
      (node (ref "S79") (pin "SW2") (pinfunction "PIN-2_SW2") (pintype "passive"))
    )
    (net (code "198") (name "Net-(S80A-PIN-1)") (class "Default")
      (node (ref "JA80") (pin "1") (pinfunction "1_1") (pintype "passive"))
      (node (ref "S80") (pin "SW1") (pinfunction "PIN-1_SW1") (pintype "passive"))
    )
    (net (code "199") (name "Net-(S80A-PIN-2)") (class "Default")
      (node (ref "JB80") (pin "2") (pinfunction "2_2") (pintype "passive"))
      (node (ref "S80") (pin "SW2") (pinfunction "PIN-2_SW2") (pintype "passive"))
    )
    (net (code "200") (name "Net-(S81A-PIN-1)") (class "Default")
      (node (ref "JA81") (pin "1") (pinfunction "1_1") (pintype "passive"))
      (node (ref "S81") (pin "SW1") (pinfunction "PIN-1_SW1") (pintype "passive"))
    )
    (net (code "201") (name "Net-(S81A-PIN-2)") (class "Default")
      (node (ref "JB81") (pin "2") (pinfunction "2_2") (pintype "passive"))
      (node (ref "S81") (pin "SW2") (pinfunction "PIN-2_SW2") (pintype "passive"))
    )
    (net (code "202") (name "Net-(S82A-PIN-1)") (class "Default")
      (node (ref "JA82") (pin "1") (pinfunction "1_1") (pintype "passive"))
      (node (ref "S82") (pin "SW2") (pinfunction "PIN-2_SW2") (pintype "passive"))
      (node (ref "S82A") (pin "SW1") (pinfunction "PIN-1_SW1") (pintype "passive"))
    )
    (net (code "203") (name "Net-(S82A-PIN-1)_1") (class "Default")
      (node (ref "JB82") (pin "2") (pinfunction "2_2") (pintype "passive"))
      (node (ref "S82") (pin "SW1") (pinfunction "PIN-1_SW1") (pintype "passive"))
      (node (ref "S82A") (pin "SW2") (pinfunction "PIN-2_SW2") (pintype "passive"))
    )
    (net (code "204") (name "Net-(S84A-PIN-1)") (class "Default")
      (node (ref "JA84") (pin "1") (pinfunction "1_1") (pintype "passive"))
      (node (ref "S84") (pin "SW1") (pinfunction "PIN-1_SW1") (pintype "passive"))
    )
    (net (code "205") (name "Net-(S84A-PIN-2)") (class "Default")
      (node (ref "JB84") (pin "2") (pinfunction "2_2") (pintype "passive"))
      (node (ref "S84") (pin "SW2") (pinfunction "PIN-2_SW2") (pintype "passive"))
    )
    (net (code "206") (name "Net-(S85A-PIN-1)") (class "Default")
      (node (ref "JA85") (pin "1") (pinfunction "1_1") (pintype "passive"))
      (node (ref "S85") (pin "SW1") (pinfunction "PIN-1_SW1") (pintype "passive"))
    )
    (net (code "207") (name "Net-(S85A-PIN-2)") (class "Default")
      (node (ref "JB85") (pin "2") (pinfunction "2_2") (pintype "passive"))
      (node (ref "S85") (pin "SW2") (pinfunction "PIN-2_SW2") (pintype "passive"))
    )
    (net (code "208") (name "Net-(S86A-PIN-1)") (class "Default")
      (node (ref "JB86") (pin "2") (pinfunction "2_2") (pintype "passive"))
      (node (ref "S86") (pin "SW1") (pinfunction "PIN-1_SW1") (pintype "passive"))
    )
    (net (code "209") (name "Net-(S86A-PIN-2)") (class "Default")
      (node (ref "JA86") (pin "1") (pinfunction "1_1") (pintype "passive"))
      (node (ref "S86") (pin "SW2") (pinfunction "PIN-2_SW2") (pintype "passive"))
    )
  )
)
